# main_board.net
KiCad netlist of a schematic drawn in EAGLE
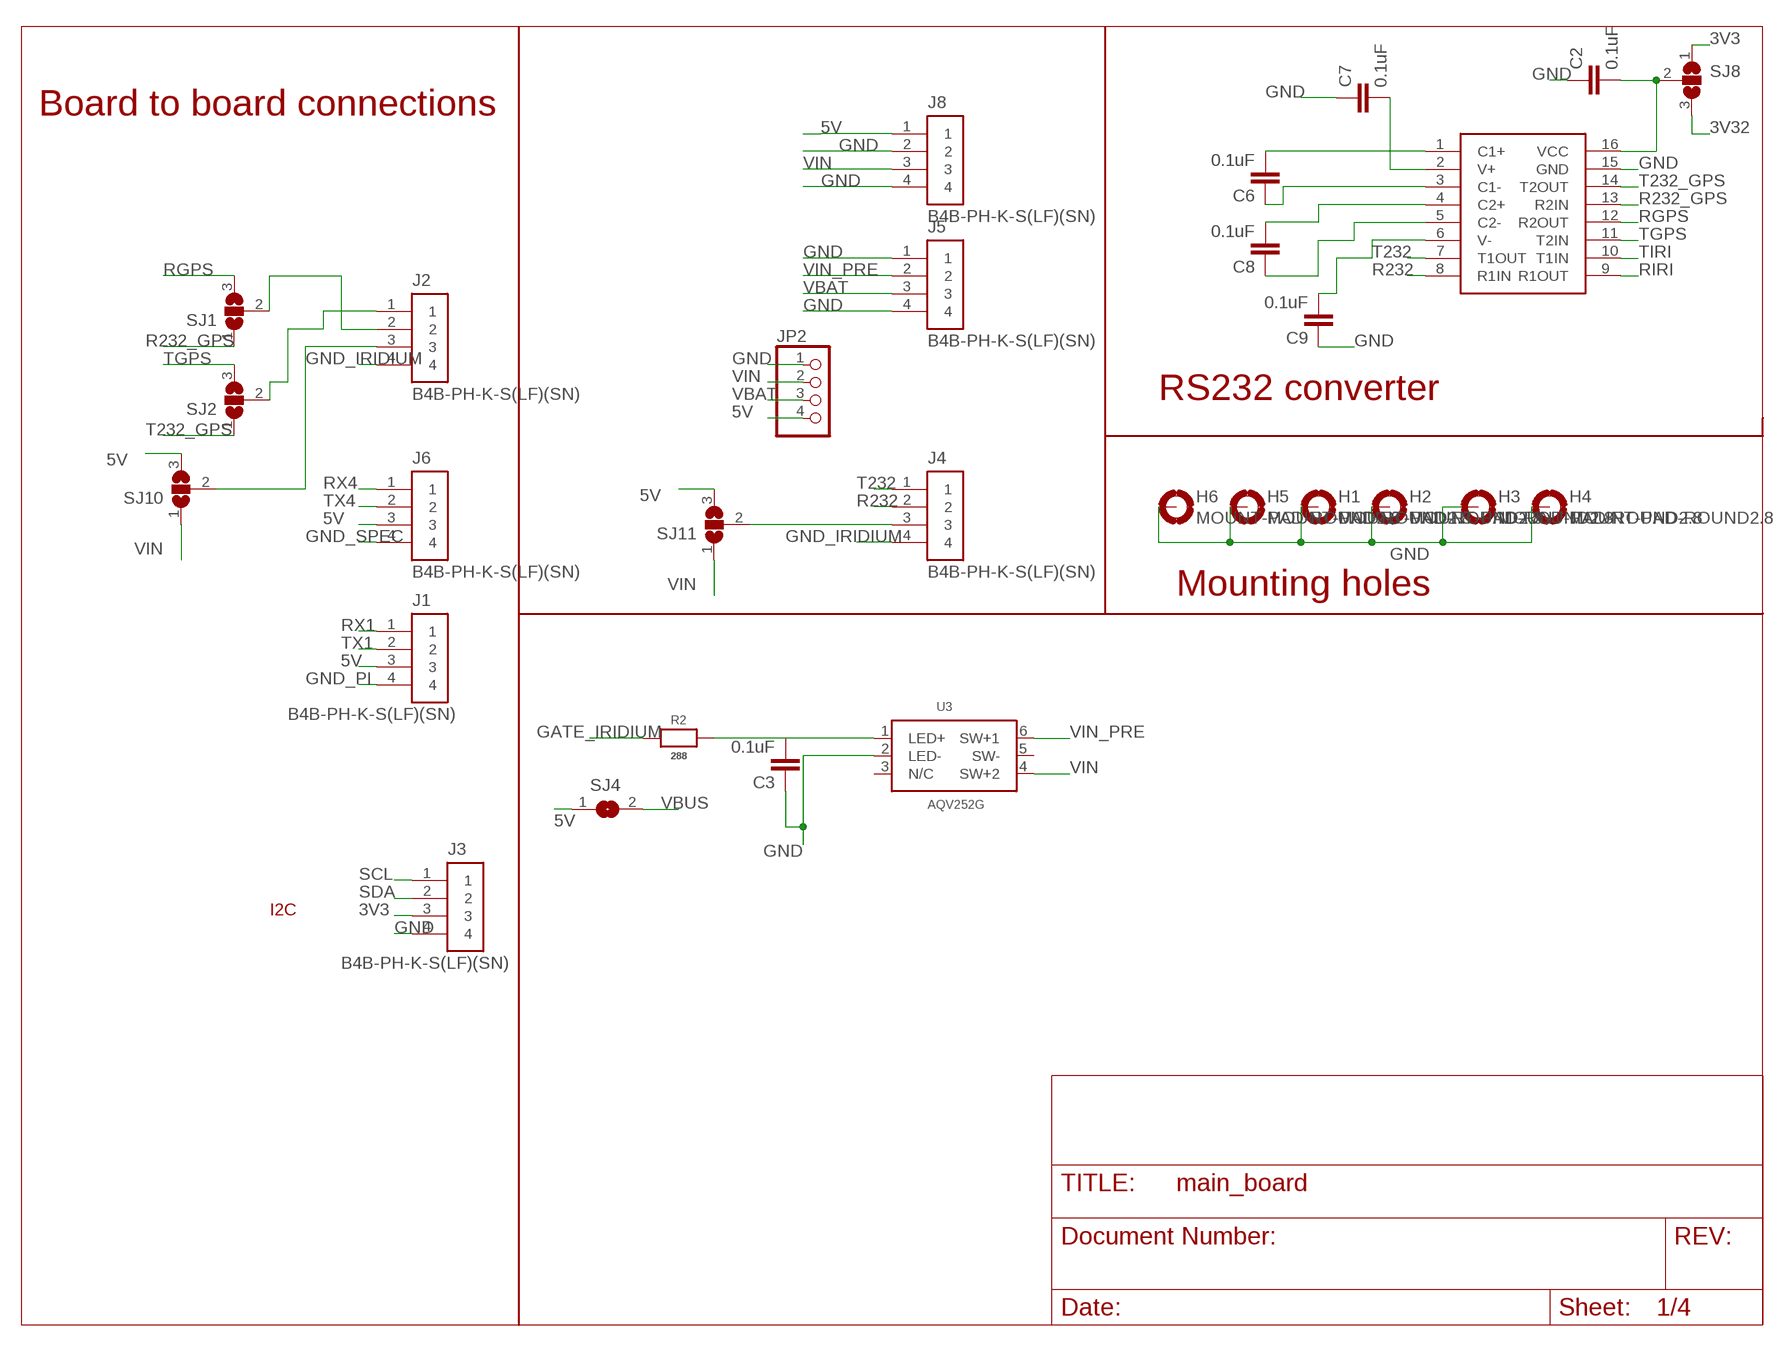
[diagram p0: schematic, sheet 1]
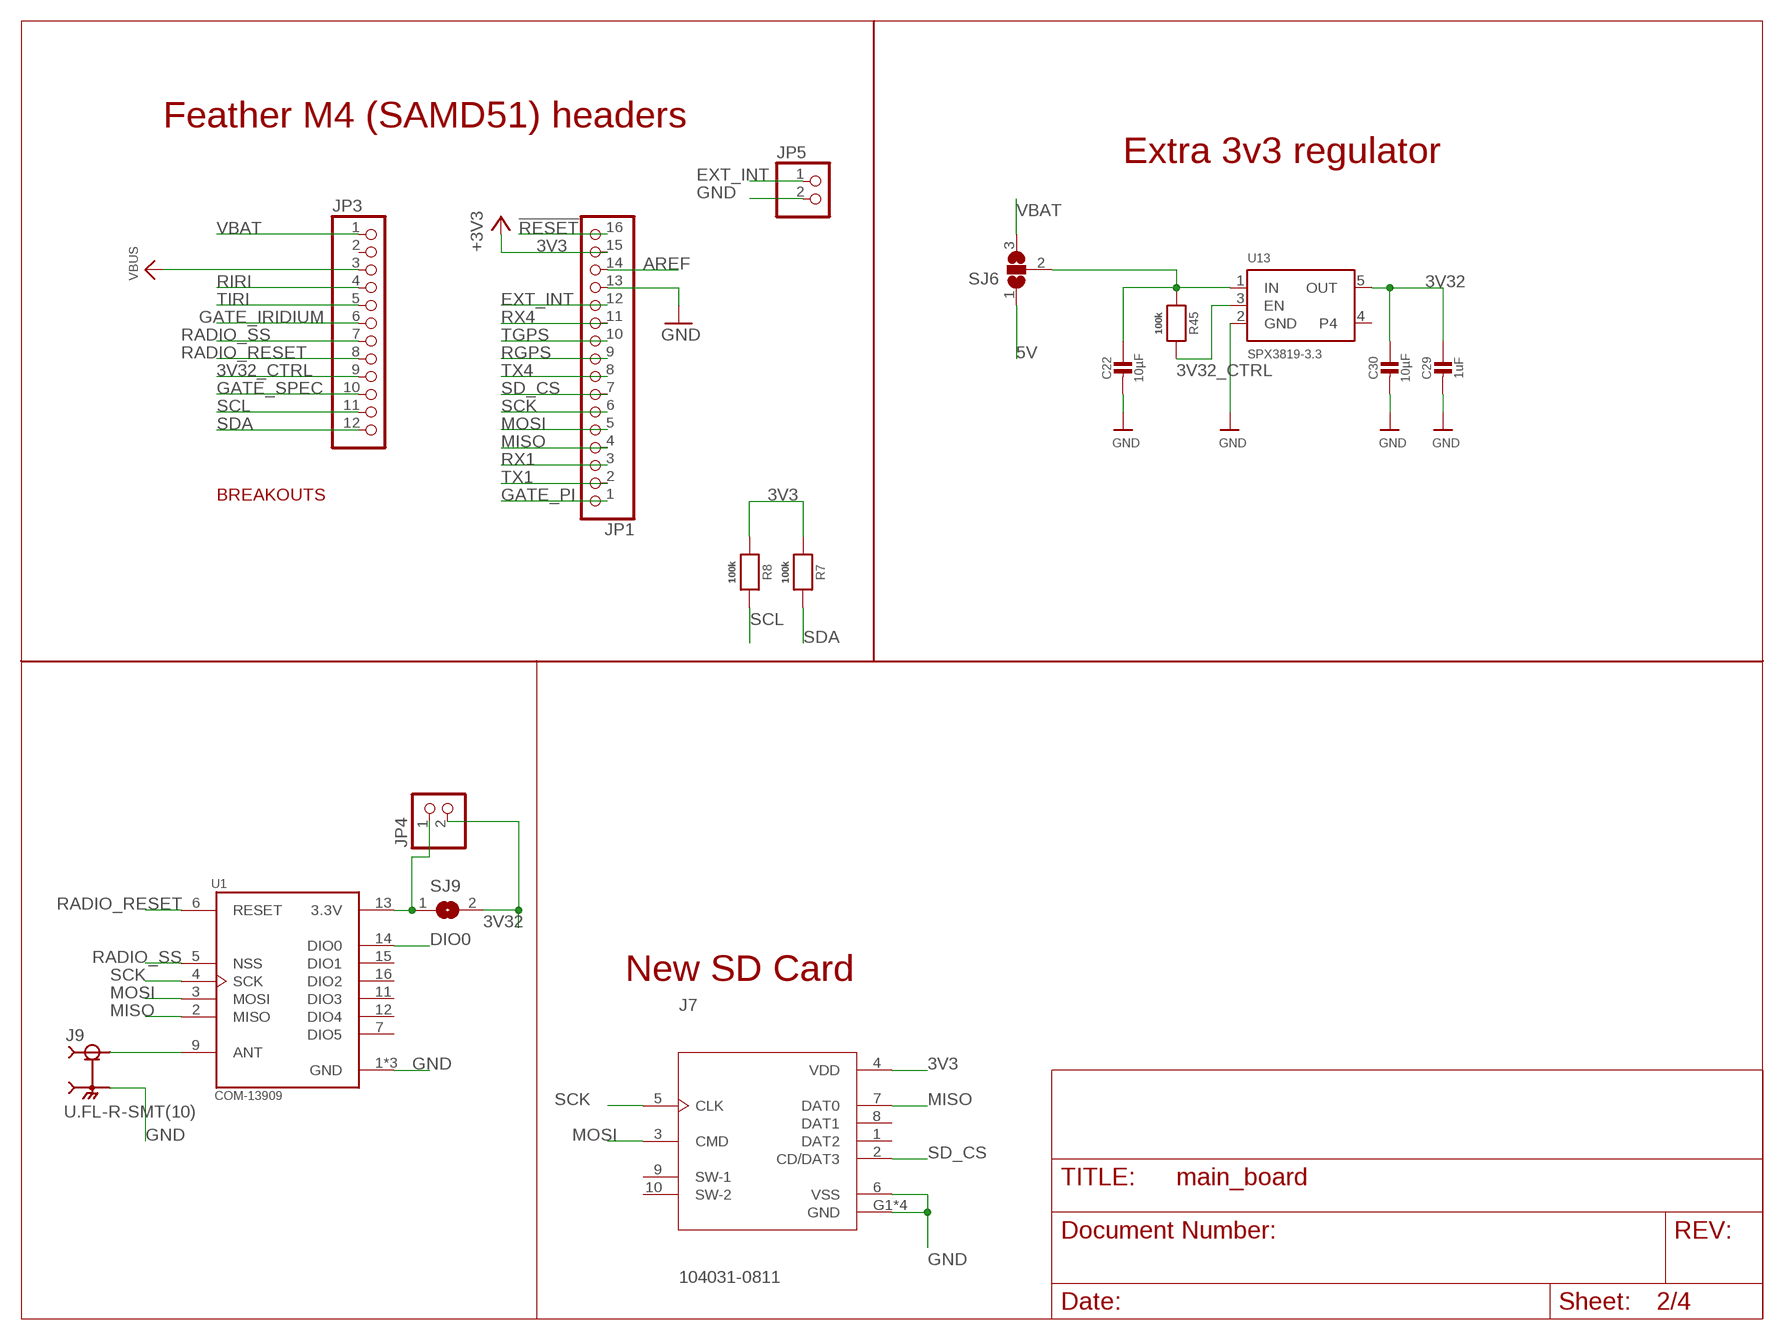
[diagram p1: schematic, sheet 2]
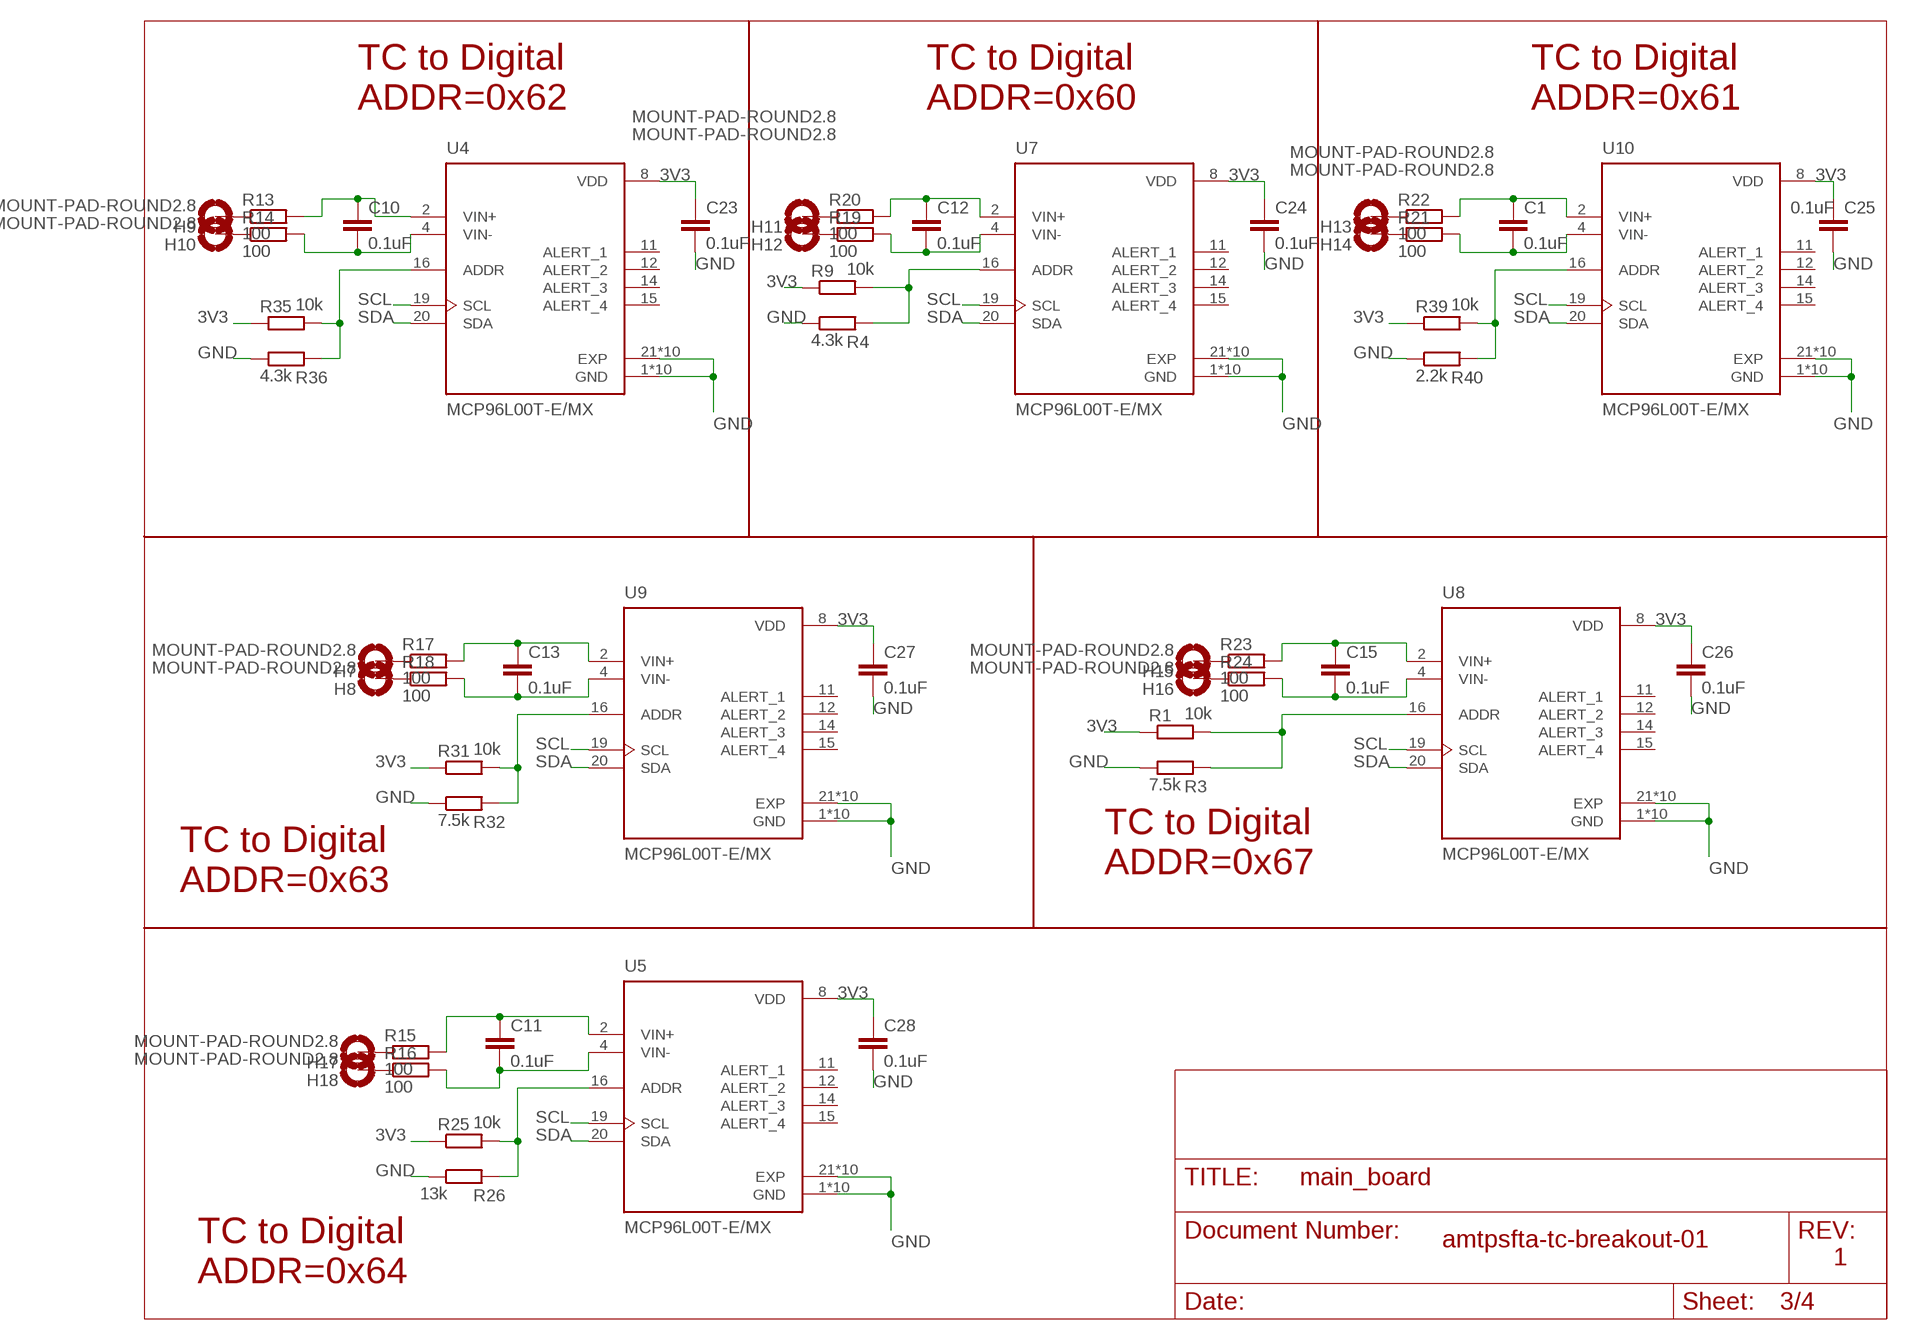
[diagram p2: schematic, sheet 3]
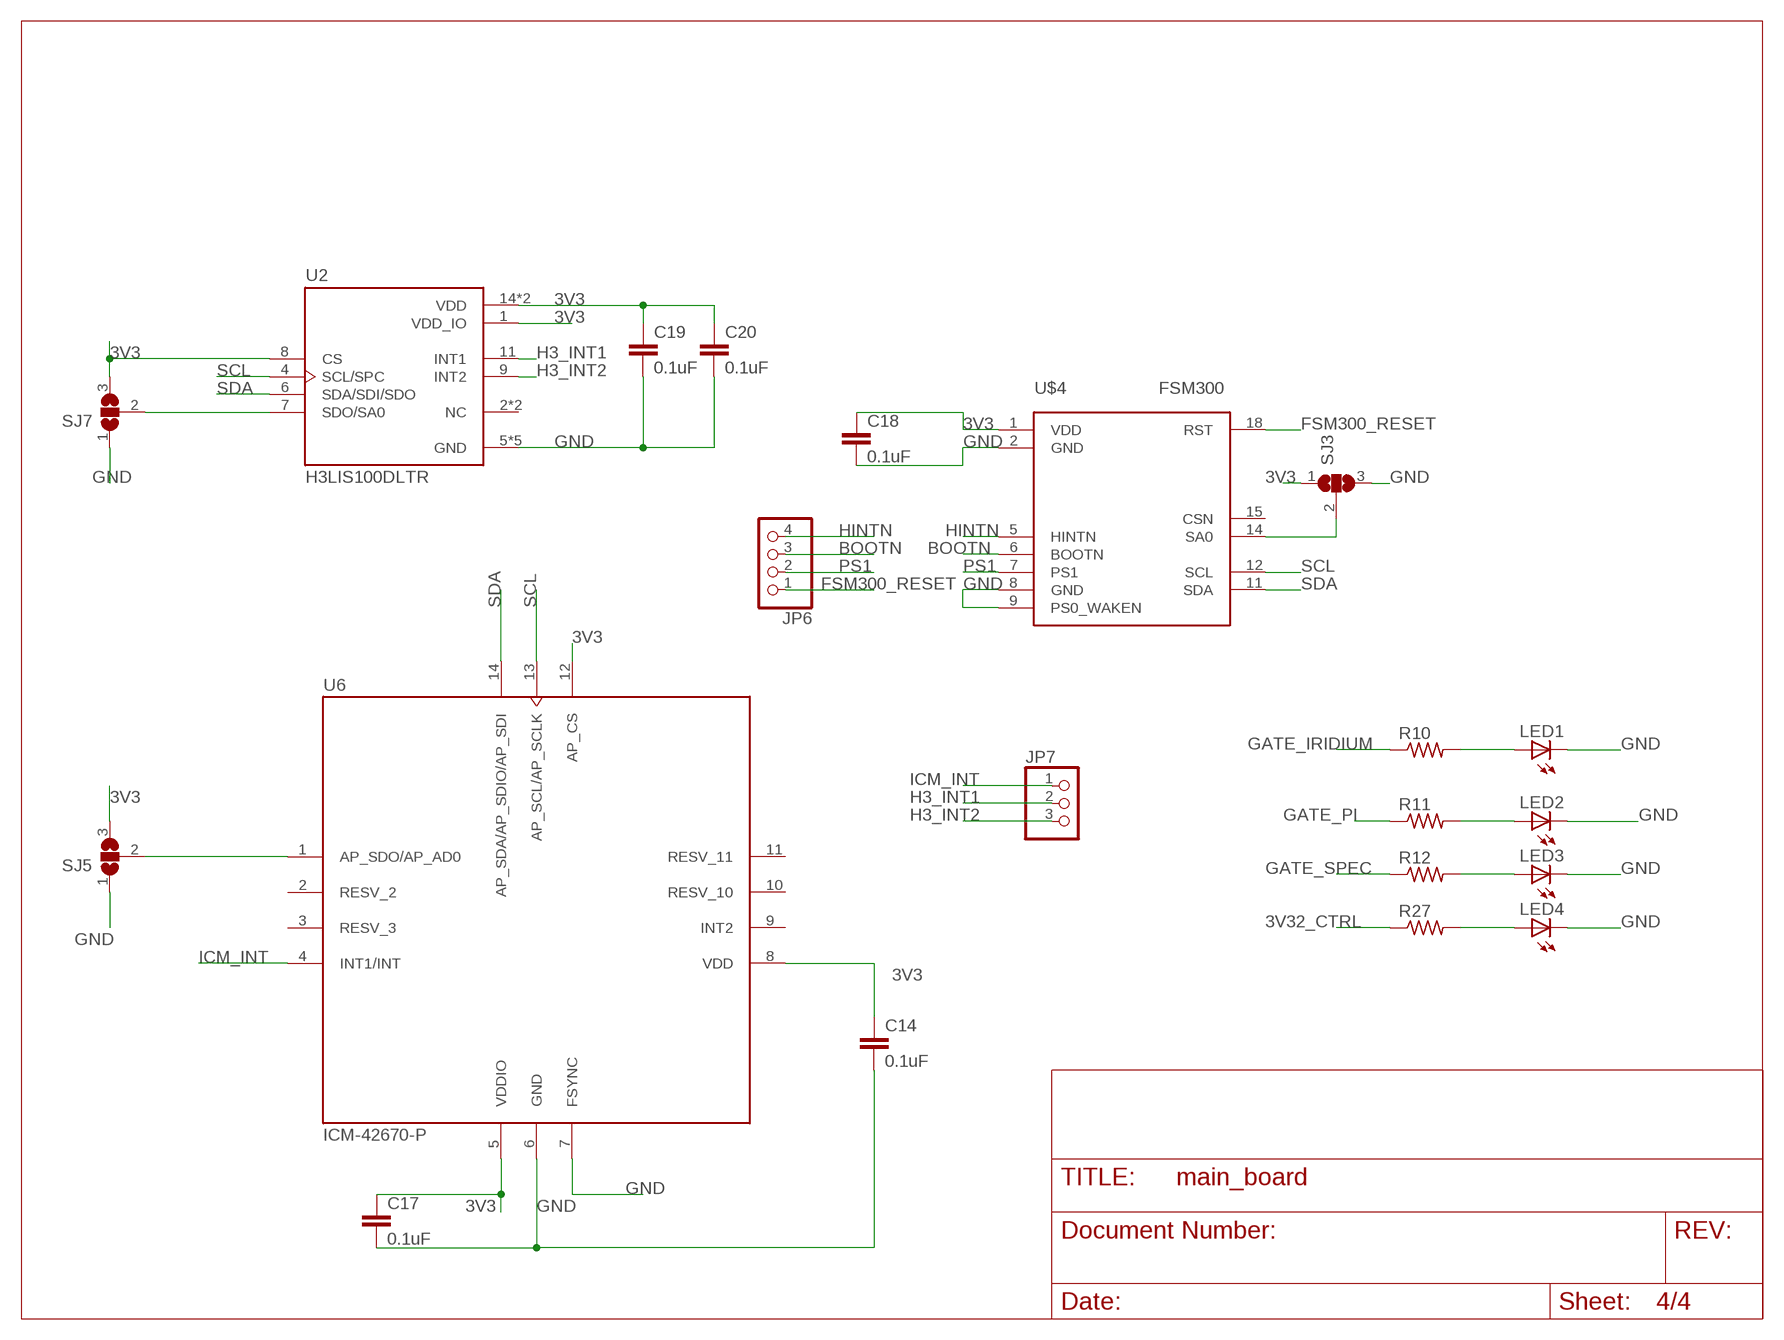
[diagram p3: schematic, sheet 4]

(export (version "E")
  (design (tool "Eeschema 10.0.6"))
  (components
    (comp (ref "C2")
      (value "0.1uF")
      (footprint "eagle-import:C0603")
      (libsource (lib "eagle-import") (part "C-EUC0603"))
    )
    (comp (ref "C3")
      (value "0.1uF")
      (footprint "eagle-import:C0603")
      (libsource (lib "eagle-import") (part "C-EUC0603"))
    )
    (comp (ref "C6")
      (value "0.1uF")
      (footprint "eagle-import:C0603")
      (libsource (lib "eagle-import") (part "C-EUC0603"))
    )
    (comp (ref "C7")
      (value "0.1uF")
      (footprint "eagle-import:C0603")
      (libsource (lib "eagle-import") (part "C-EUC0603"))
    )
    (comp (ref "C8")
      (value "0.1uF")
      (footprint "eagle-import:C0603")
      (libsource (lib "eagle-import") (part "C-EUC0603"))
    )
    (comp (ref "C9")
      (value "0.1uF")
      (footprint "eagle-import:C0603")
      (libsource (lib "eagle-import") (part "C-EUC0603"))
    )
    (comp (ref "H1")
      (value "MOUNT-PAD-ROUND2.8")
      (footprint "eagle-import:2,8-PAD")
      (libsource (lib "eagle-import") (part "MOUNT-PAD-ROUND2.8"))
    )
    (comp (ref "H2")
      (value "MOUNT-PAD-ROUND2.8")
      (footprint "eagle-import:2,8-PAD")
      (libsource (lib "eagle-import") (part "MOUNT-PAD-ROUND2.8"))
    )
    (comp (ref "H3")
      (value "MOUNT-PAD-ROUND2.8")
      (footprint "eagle-import:2,8-PAD")
      (libsource (lib "eagle-import") (part "MOUNT-PAD-ROUND2.8"))
    )
    (comp (ref "H4")
      (value "MOUNT-PAD-ROUND2.8")
      (footprint "eagle-import:2,8-PAD")
      (libsource (lib "eagle-import") (part "MOUNT-PAD-ROUND2.8"))
    )
    (comp (ref "H5")
      (value "MOUNT-PAD-ROUND2.8")
      (footprint "eagle-import:2,8-PAD")
      (libsource (lib "eagle-import") (part "MOUNT-PAD-ROUND2.8"))
    )
    (comp (ref "H6")
      (value "MOUNT-PAD-ROUND2.8")
      (footprint "eagle-import:2,8-PAD")
      (libsource (lib "eagle-import") (part "MOUNT-PAD-ROUND2.8"))
    )
    (comp (ref "J1")
      (value "B4B-PH-K-S(LF)(SN)")
      (footprint "eagle-import:JST_B4B-PH-K-S(LF)(SN)")
      (fields (field (name "DIGI-KEY_PART_NUMBER") "455-1706-ND") (field (name "MF") "JST"))
      (libsource (lib "eagle-import") (part "B4B-PH-K-S(LF)(SN)"))
    )
    (comp (ref "J2")
      (value "B4B-PH-K-S(LF)(SN)")
      (footprint "eagle-import:JST_B4B-PH-K-S(LF)(SN)")
      (fields (field (name "DIGI-KEY_PART_NUMBER") "455-1706-ND") (field (name "MF") "JST"))
      (libsource (lib "eagle-import") (part "B4B-PH-K-S(LF)(SN)"))
    )
    (comp (ref "J3")
      (value "B4B-PH-K-S(LF)(SN)")
      (footprint "eagle-import:JST_B4B-PH-K-S(LF)(SN)")
      (fields (field (name "DIGI-KEY_PART_NUMBER") "455-1706-ND") (field (name "MF") "JST"))
      (libsource (lib "eagle-import") (part "B4B-PH-K-S(LF)(SN)"))
    )
    (comp (ref "J4")
      (value "B4B-PH-K-S(LF)(SN)")
      (footprint "eagle-import:JST_B4B-PH-K-S(LF)(SN)")
      (fields (field (name "DIGI-KEY_PART_NUMBER") "455-1706-ND") (field (name "MF") "JST"))
      (libsource (lib "eagle-import") (part "B4B-PH-K-S(LF)(SN)"))
    )
    (comp (ref "J5")
      (value "B4B-PH-K-S(LF)(SN)")
      (footprint "eagle-import:JST_B4B-PH-K-S(LF)(SN)")
      (fields (field (name "DIGI-KEY_PART_NUMBER") "455-1706-ND") (field (name "MF") "JST"))
      (libsource (lib "eagle-import") (part "B4B-PH-K-S(LF)(SN)"))
    )
    (comp (ref "J6")
      (value "B4B-PH-K-S(LF)(SN)")
      (footprint "eagle-import:JST_B4B-PH-K-S(LF)(SN)")
      (fields (field (name "DIGI-KEY_PART_NUMBER") "455-1706-ND") (field (name "MF") "JST"))
      (libsource (lib "eagle-import") (part "B4B-PH-K-S(LF)(SN)"))
    )
    (comp (ref "J8")
      (value "B4B-PH-K-S(LF)(SN)")
      (footprint "eagle-import:JST_B4B-PH-K-S(LF)(SN)")
      (fields (field (name "DIGI-KEY_PART_NUMBER") "455-1706-ND") (field (name "MF") "JST"))
      (libsource (lib "eagle-import") (part "B4B-PH-K-S(LF)(SN)"))
    )
    (comp (ref "JP2")
      (value "PINHD-1X4")
      (footprint "eagle-import:1X04")
      (libsource (lib "eagle-import") (part "PINHD-1X4"))
    )
    (comp (ref "R2")
      (value "288")
      (footprint "eagle-import:0603-NO")
      (libsource (lib "eagle-import") (part "RESISTOR_0603_NOOUT"))
    )
    (comp (ref "SJ1")
      (value "SJ2W")
      (footprint "eagle-import:SJ_2")
      (libsource (lib "eagle-import") (part "SJ2W"))
    )
    (comp (ref "SJ2")
      (value "SJ2W")
      (footprint "eagle-import:SJ_2")
      (libsource (lib "eagle-import") (part "SJ2W"))
    )
    (comp (ref "SJ4") (value "SJ") (footprint "eagle-import:SJ") (libsource (lib "eagle-import") (part "SJ")))
    (comp (ref "SJ8")
      (value "SJ2W")
      (footprint "eagle-import:SJ_2")
      (libsource (lib "eagle-import") (part "SJ2W"))
    )
    (comp (ref "SJ10")
      (value "SJ2W")
      (footprint "eagle-import:SJ_2")
      (libsource (lib "eagle-import") (part "SJ2W"))
    )
    (comp (ref "SJ11")
      (value "SJ2W")
      (footprint "eagle-import:SJ_2")
      (libsource (lib "eagle-import") (part "SJ2W"))
    )
    (comp (ref "U3")
      (value "AQV252G")
      (footprint "eagle-import:SOP6")
      (fields (field (name "DIGI-KEY_PART_NUMBER") "255-1791-5-ND") (field (name "MF") "Panasonic"))
      (libsource (lib "eagle-import") (part "AQV252G"))
    )
    (comp (ref "U11")
      (value "UM3232EEAE")
      (footprint "eagle-import:RQ_16_ADI")
      (libsource (lib "eagle-import") (part "UM3232EEAE"))
    )
    (comp (ref "C1")
      (value "0.1uF")
      (footprint "eagle-import:C0603")
      (libsource (lib "eagle-import") (part "C-EUC0603"))
    )
    (comp (ref "C10")
      (value "0.1uF")
      (footprint "eagle-import:C0603")
      (libsource (lib "eagle-import") (part "C-EUC0603"))
    )
    (comp (ref "C11")
      (value "0.1uF")
      (footprint "eagle-import:C0603")
      (libsource (lib "eagle-import") (part "C-EUC0603"))
    )
    (comp (ref "C12")
      (value "0.1uF")
      (footprint "eagle-import:C0603")
      (libsource (lib "eagle-import") (part "C-EUC0603"))
    )
    (comp (ref "C13")
      (value "0.1uF")
      (footprint "eagle-import:C0603")
      (libsource (lib "eagle-import") (part "C-EUC0603"))
    )
    (comp (ref "C15")
      (value "0.1uF")
      (footprint "eagle-import:C0603")
      (libsource (lib "eagle-import") (part "C-EUC0603"))
    )
    (comp (ref "C23")
      (value "0.1uF")
      (footprint "eagle-import:C0603")
      (libsource (lib "eagle-import") (part "C-EUC0603"))
    )
    (comp (ref "C24")
      (value "0.1uF")
      (footprint "eagle-import:C0603")
      (libsource (lib "eagle-import") (part "C-EUC0603"))
    )
    (comp (ref "C25")
      (value "0.1uF")
      (footprint "eagle-import:C0603")
      (libsource (lib "eagle-import") (part "C-EUC0603"))
    )
    (comp (ref "C26")
      (value "0.1uF")
      (footprint "eagle-import:C0603")
      (libsource (lib "eagle-import") (part "C-EUC0603"))
    )
    (comp (ref "C27")
      (value "0.1uF")
      (footprint "eagle-import:C0603")
      (libsource (lib "eagle-import") (part "C-EUC0603"))
    )
    (comp (ref "C28")
      (value "0.1uF")
      (footprint "eagle-import:C0603")
      (libsource (lib "eagle-import") (part "C-EUC0603"))
    )
    (comp (ref "H7")
      (value "MOUNT-PAD-ROUND2.8")
      (footprint "eagle-import:2,8-PAD")
      (libsource (lib "eagle-import") (part "MOUNT-PAD-ROUND2.8"))
    )
    (comp (ref "H8")
      (value "MOUNT-PAD-ROUND2.8")
      (footprint "eagle-import:2,8-PAD")
      (libsource (lib "eagle-import") (part "MOUNT-PAD-ROUND2.8"))
    )
    (comp (ref "H9")
      (value "MOUNT-PAD-ROUND2.8")
      (footprint "eagle-import:2,8-PAD")
      (libsource (lib "eagle-import") (part "MOUNT-PAD-ROUND2.8"))
    )
    (comp (ref "H10")
      (value "MOUNT-PAD-ROUND2.8")
      (footprint "eagle-import:2,8-PAD")
      (libsource (lib "eagle-import") (part "MOUNT-PAD-ROUND2.8"))
    )
    (comp (ref "H11")
      (value "MOUNT-PAD-ROUND2.8")
      (footprint "eagle-import:2,8-PAD")
      (libsource (lib "eagle-import") (part "MOUNT-PAD-ROUND2.8"))
    )
    (comp (ref "H12")
      (value "MOUNT-PAD-ROUND2.8")
      (footprint "eagle-import:2,8-PAD")
      (libsource (lib "eagle-import") (part "MOUNT-PAD-ROUND2.8"))
    )
    (comp (ref "H13")
      (value "MOUNT-PAD-ROUND2.8")
      (footprint "eagle-import:2,8-PAD")
      (libsource (lib "eagle-import") (part "MOUNT-PAD-ROUND2.8"))
    )
    (comp (ref "H14")
      (value "MOUNT-PAD-ROUND2.8")
      (footprint "eagle-import:2,8-PAD")
      (libsource (lib "eagle-import") (part "MOUNT-PAD-ROUND2.8"))
    )
    (comp (ref "H15")
      (value "MOUNT-PAD-ROUND2.8")
      (footprint "eagle-import:2,8-PAD")
      (libsource (lib "eagle-import") (part "MOUNT-PAD-ROUND2.8"))
    )
    (comp (ref "H16")
      (value "MOUNT-PAD-ROUND2.8")
      (footprint "eagle-import:2,8-PAD")
      (libsource (lib "eagle-import") (part "MOUNT-PAD-ROUND2.8"))
    )
    (comp (ref "H17")
      (value "MOUNT-PAD-ROUND2.8")
      (footprint "eagle-import:2,8-PAD")
      (libsource (lib "eagle-import") (part "MOUNT-PAD-ROUND2.8"))
    )
    (comp (ref "H18")
      (value "MOUNT-PAD-ROUND2.8")
      (footprint "eagle-import:2,8-PAD")
      (libsource (lib "eagle-import") (part "MOUNT-PAD-ROUND2.8"))
    )
    (comp (ref "R1")
      (value "10k")
      (footprint "eagle-import:R0603")
      (libsource (lib "eagle-import") (part "R-EU_R0603"))
    )
    (comp (ref "R3")
      (value "7.5k")
      (footprint "eagle-import:R0603")
      (libsource (lib "eagle-import") (part "R-EU_R0603"))
    )
    (comp (ref "R4")
      (value "4.3k")
      (footprint "eagle-import:R0603")
      (libsource (lib "eagle-import") (part "R-EU_R0603"))
    )
    (comp (ref "R9")
      (value "10k")
      (footprint "eagle-import:R0603")
      (libsource (lib "eagle-import") (part "R-EU_R0603"))
    )
    (comp (ref "R13")
      (value "100")
      (footprint "eagle-import:R0603")
      (libsource (lib "eagle-import") (part "R-EU_R0603"))
    )
    (comp (ref "R14")
      (value "100")
      (footprint "eagle-import:R0603")
      (libsource (lib "eagle-import") (part "R-EU_R0603"))
    )
    (comp (ref "R15")
      (value "100")
      (footprint "eagle-import:R0603")
      (libsource (lib "eagle-import") (part "R-EU_R0603"))
    )
    (comp (ref "R16")
      (value "100")
      (footprint "eagle-import:R0603")
      (libsource (lib "eagle-import") (part "R-EU_R0603"))
    )
    (comp (ref "R17")
      (value "100")
      (footprint "eagle-import:R0603")
      (libsource (lib "eagle-import") (part "R-EU_R0603"))
    )
    (comp (ref "R18")
      (value "100")
      (footprint "eagle-import:R0603")
      (libsource (lib "eagle-import") (part "R-EU_R0603"))
    )
    (comp (ref "R19")
      (value "100")
      (footprint "eagle-import:R0603")
      (libsource (lib "eagle-import") (part "R-EU_R0603"))
    )
    (comp (ref "R20")
      (value "100")
      (footprint "eagle-import:R0603")
      (libsource (lib "eagle-import") (part "R-EU_R0603"))
    )
    (comp (ref "R21")
      (value "100")
      (footprint "eagle-import:R0603")
      (libsource (lib "eagle-import") (part "R-EU_R0603"))
    )
    (comp (ref "R22")
      (value "100")
      (footprint "eagle-import:R0603")
      (libsource (lib "eagle-import") (part "R-EU_R0603"))
    )
    (comp (ref "R23")
      (value "100")
      (footprint "eagle-import:R0603")
      (libsource (lib "eagle-import") (part "R-EU_R0603"))
    )
    (comp (ref "R24")
      (value "100")
      (footprint "eagle-import:R0603")
      (libsource (lib "eagle-import") (part "R-EU_R0603"))
    )
    (comp (ref "R25")
      (value "10k")
      (footprint "eagle-import:R0603")
      (libsource (lib "eagle-import") (part "R-EU_R0603"))
    )
    (comp (ref "R26")
      (value "13k")
      (footprint "eagle-import:R0603")
      (libsource (lib "eagle-import") (part "R-EU_R0603"))
    )
    (comp (ref "R31")
      (value "10k")
      (footprint "eagle-import:R0603")
      (libsource (lib "eagle-import") (part "R-EU_R0603"))
    )
    (comp (ref "R32")
      (value "7.5k")
      (footprint "eagle-import:R0603")
      (libsource (lib "eagle-import") (part "R-EU_R0603"))
    )
    (comp (ref "R35")
      (value "10k")
      (footprint "eagle-import:R0603")
      (libsource (lib "eagle-import") (part "R-EU_R0603"))
    )
    (comp (ref "R36")
      (value "4.3k")
      (footprint "eagle-import:R0603")
      (libsource (lib "eagle-import") (part "R-EU_R0603"))
    )
    (comp (ref "R39")
      (value "10k")
      (footprint "eagle-import:R0603")
      (libsource (lib "eagle-import") (part "R-EU_R0603"))
    )
    (comp (ref "R40")
      (value "2.2k")
      (footprint "eagle-import:R0603")
      (libsource (lib "eagle-import") (part "R-EU_R0603"))
    )
    (comp (ref "U4")
      (value "MCP96L00T-E/MX")
      (footprint "eagle-import:QFN65P500X500X100-21N_MCP96L00T-E_MX")
      (fields
        (field (name "DIGI-KEY_PART_NUMBER") "MCP96L00T-E/MXCT-ND")
        (field (name "MF") "Microchip Technology")
      )
      (libsource (lib "eagle-import") (part "MCP96L00T-E/MX"))
    )
    (comp (ref "U5")
      (value "MCP96L00T-E/MX")
      (footprint "eagle-import:QFN65P500X500X100-21N_MCP96L00T-E_MX")
      (fields
        (field (name "DIGI-KEY_PART_NUMBER") "MCP96L00T-E/MXCT-ND")
        (field (name "MF") "Microchip Technology")
      )
      (libsource (lib "eagle-import") (part "MCP96L00T-E/MX"))
    )
    (comp (ref "U7")
      (value "MCP96L00T-E/MX")
      (footprint "eagle-import:QFN65P500X500X100-21N_MCP96L00T-E_MX")
      (fields
        (field (name "DIGI-KEY_PART_NUMBER") "MCP96L00T-E/MXCT-ND")
        (field (name "MF") "Microchip Technology")
      )
      (libsource (lib "eagle-import") (part "MCP96L00T-E/MX"))
    )
    (comp (ref "U8")
      (value "MCP96L00T-E/MX")
      (footprint "eagle-import:QFN65P500X500X100-21N_MCP96L00T-E_MX")
      (fields
        (field (name "DIGI-KEY_PART_NUMBER") "MCP96L00T-E/MXCT-ND")
        (field (name "MF") "Microchip Technology")
      )
      (libsource (lib "eagle-import") (part "MCP96L00T-E/MX"))
    )
    (comp (ref "U9")
      (value "MCP96L00T-E/MX")
      (footprint "eagle-import:QFN65P500X500X100-21N_MCP96L00T-E_MX")
      (fields
        (field (name "DIGI-KEY_PART_NUMBER") "MCP96L00T-E/MXCT-ND")
        (field (name "MF") "Microchip Technology")
      )
      (libsource (lib "eagle-import") (part "MCP96L00T-E/MX"))
    )
    (comp (ref "U10")
      (value "MCP96L00T-E/MX")
      (footprint "eagle-import:QFN65P500X500X100-21N_MCP96L00T-E_MX")
      (fields
        (field (name "DIGI-KEY_PART_NUMBER") "MCP96L00T-E/MXCT-ND")
        (field (name "MF") "Microchip Technology")
      )
      (libsource (lib "eagle-import") (part "MCP96L00T-E/MX"))
    )
    (comp (ref "C22")
      (value "10µF")
      (footprint "eagle-import:0805-NO")
      (libsource (lib "eagle-import") (part "CAP_CERAMIC0805-NOOUTLINE"))
    )
    (comp (ref "C29")
      (value "1uF")
      (footprint "eagle-import:0603-NO")
      (libsource (lib "eagle-import") (part "CAP_CERAMIC0603_NO"))
    )
    (comp (ref "C30")
      (value "10µF")
      (footprint "eagle-import:0805-NO")
      (libsource (lib "eagle-import") (part "CAP_CERAMIC0805-NOOUTLINE"))
    )
    (comp (ref "J7")
      (value "104031-0811")
      (footprint "eagle-import:MOLEX_104031-0811")
      (fields (field (name "DIGI-KEY_PART_NUMBER") "WM6357TR-ND") (field (name "MF") "Molex"))
      (libsource (lib "eagle-import") (part "104031-0811"))
    )
    (comp (ref "J9")
      (value "U.FL-R-SMT(10)")
      (footprint "eagle-import:HRS_U.FL-R-SMT(10)")
      (fields (field (name "DIGI-KEY_PART_NUMBER") "H9161TR-ND") (field (name "MF") "Hirose Electric Co Ltd"))
      (libsource (lib "eagle-import") (part "U.FL-R-SMT(10)"))
    )
    (comp (ref "JP1")
      (value "HEADER-1X16ROUND")
      (footprint "eagle-import:1X16_ROUND")
      (libsource (lib "eagle-import") (part "HEADER-1X16ROUND"))
    )
    (comp (ref "JP3")
      (value "HEADER-1X12")
      (footprint "eagle-import:1X12_ROUND")
      (libsource (lib "eagle-import") (part "HEADER-1X12"))
    )
    (comp (ref "JP4")
      (value "PINHD-1X2")
      (footprint "eagle-import:1X02")
      (libsource (lib "eagle-import") (part "PINHD-1X2"))
    )
    (comp (ref "JP5")
      (value "PINHD-1X2")
      (footprint "eagle-import:1X02")
      (libsource (lib "eagle-import") (part "PINHD-1X2"))
    )
    (comp (ref "R7")
      (value "100k")
      (footprint "eagle-import:0603-NO")
      (libsource (lib "eagle-import") (part "RESISTOR_0603_NOOUT"))
    )
    (comp (ref "R8")
      (value "100k")
      (footprint "eagle-import:0603-NO")
      (libsource (lib "eagle-import") (part "RESISTOR_0603_NOOUT"))
    )
    (comp (ref "R45")
      (value "100k")
      (footprint "eagle-import:0603-NO")
      (libsource (lib "eagle-import") (part "RESISTOR_0603_NOOUT"))
    )
    (comp (ref "SJ6")
      (value "SJ2W")
      (footprint "eagle-import:SJ_2")
      (libsource (lib "eagle-import") (part "SJ2W"))
    )
    (comp (ref "SJ9") (value "SJ") (footprint "eagle-import:SJ") (libsource (lib "eagle-import") (part "SJ")))
    (comp (ref "U1")
      (value "COM-13909")
      (footprint "eagle-import:MOD_COM-13909")
      (fields (field (name "DIGI-KEY_PART_NUMBER") "1568-1394-ND") (field (name "MF") "SparkFun Electronics"))
      (libsource (lib "eagle-import") (part "COM-13909"))
    )
    (comp (ref "U13")
      (value "SPX3819-3.3")
      (footprint "eagle-import:SOT23-5")
      (libsource (lib "eagle-import") (part "VREG_SOT23-5"))
    )
    (comp (ref "C14")
      (value "0.1uF")
      (footprint "eagle-import:C0603")
      (libsource (lib "eagle-import") (part "C-EUC0603"))
    )
    (comp (ref "C17")
      (value "0.1uF")
      (footprint "eagle-import:C0603")
      (libsource (lib "eagle-import") (part "C-EUC0603"))
    )
    (comp (ref "C18")
      (value "0.1uF")
      (footprint "eagle-import:C0603")
      (libsource (lib "eagle-import") (part "C-EUC0603"))
    )
    (comp (ref "C19")
      (value "0.1uF")
      (footprint "eagle-import:C0603")
      (libsource (lib "eagle-import") (part "C-EUC0603"))
    )
    (comp (ref "C20")
      (value "0.1uF")
      (footprint "eagle-import:C0603")
      (libsource (lib "eagle-import") (part "C-EUC0603"))
    )
    (comp (ref "JP6")
      (value "PINHD-1X4")
      (footprint "eagle-import:1X04")
      (libsource (lib "eagle-import") (part "PINHD-1X4"))
    )
    (comp (ref "JP7")
      (value "PINHD-1X3")
      (footprint "eagle-import:1X03")
      (libsource (lib "eagle-import") (part "PINHD-1X3"))
    )
    (comp (ref "LED1")
      (value "LEDCHIPLED_0603")
      (footprint "eagle-import:CHIPLED_0603")
      (libsource (lib "eagle-import") (part "LEDCHIPLED_0603"))
    )
    (comp (ref "LED2")
      (value "LEDCHIPLED_0603")
      (footprint "eagle-import:CHIPLED_0603")
      (libsource (lib "eagle-import") (part "LEDCHIPLED_0603"))
    )
    (comp (ref "LED3")
      (value "LEDCHIPLED_0603")
      (footprint "eagle-import:CHIPLED_0603")
      (libsource (lib "eagle-import") (part "LEDCHIPLED_0603"))
    )
    (comp (ref "LED4")
      (value "LEDCHIPLED_0603")
      (footprint "eagle-import:CHIPLED_0603")
      (libsource (lib "eagle-import") (part "LEDCHIPLED_0603"))
    )
    (comp (ref "R10")
      (value "R-US_R0603")
      (footprint "eagle-import:R0603")
      (libsource (lib "eagle-import") (part "R-US_R0603"))
    )
    (comp (ref "R11")
      (value "R-US_R0603")
      (footprint "eagle-import:R0603")
      (libsource (lib "eagle-import") (part "R-US_R0603"))
    )
    (comp (ref "R12")
      (value "R-US_R0603")
      (footprint "eagle-import:R0603")
      (libsource (lib "eagle-import") (part "R-US_R0603"))
    )
    (comp (ref "R27")
      (value "R-US_R0603")
      (footprint "eagle-import:R0603")
      (libsource (lib "eagle-import") (part "R-US_R0603"))
    )
    (comp (ref "SJ3")
      (value "SJ2W")
      (footprint "eagle-import:SJ_2")
      (libsource (lib "eagle-import") (part "SJ2W"))
    )
    (comp (ref "SJ5")
      (value "SJ2W")
      (footprint "eagle-import:SJ_2")
      (libsource (lib "eagle-import") (part "SJ2W"))
    )
    (comp (ref "SJ7")
      (value "SJ2W")
      (footprint "eagle-import:SJ_2")
      (libsource (lib "eagle-import") (part "SJ2W"))
    )
    (comp (ref "U$4")
      (value "FSM300")
      (footprint "eagle-import:FSM300_FOOTPRINT")
      (libsource (lib "eagle-import") (part "FSM300"))
    )
    (comp (ref "U2")
      (value "H3LIS100DLTR")
      (footprint "eagle-import:PQFN50P300X300X100-16N")
      (fields (field (name "DIGI-KEY_PART_NUMBER") "497-15697-2-ND") (field (name "MF") "STMicroelectronics"))
      (libsource (lib "eagle-import") (part "H3LIS100DLTR"))
    )
    (comp (ref "U6")
      (value "ICM-42670-P")
      (footprint "eagle-import:IC_ICM-42670-P")
      (fields
        (field (name "DIGI-KEY_PART_NUMBER") "1428-ICM-42670-PTR-ND")
        (field (name "MF") "TDK InvenSense")
      )
      (libsource (lib "eagle-import") (part "ICM-42670-P"))
    )
  )
  (nets
    (net (code "1") (name "3V3") (class "Default")
      (node (ref "C14") (pin "1") (pinfunction "1_1") (pintype "passive"))
      (node (ref "C17") (pin "1") (pinfunction "1_1") (pintype "passive"))
      (node (ref "C18") (pin "1") (pinfunction "1_1") (pintype "passive"))
      (node (ref "C19") (pin "1") (pinfunction "1_1") (pintype "passive"))
      (node (ref "C20") (pin "1") (pinfunction "1_1") (pintype "passive"))
      (node (ref "C23") (pin "1") (pinfunction "1_1") (pintype "passive"))
      (node (ref "C24") (pin "1") (pinfunction "1_1") (pintype "passive"))
      (node (ref "C25") (pin "1") (pinfunction "1_1") (pintype "passive"))
      (node (ref "C26") (pin "1") (pinfunction "1_1") (pintype "passive"))
      (node (ref "C27") (pin "1") (pinfunction "1_1") (pintype "passive"))
      (node (ref "C28") (pin "1") (pinfunction "1_1") (pintype "passive"))
      (node (ref "J3") (pin "3") (pinfunction "3_3") (pintype "passive"))
      (node (ref "J7") (pin "4") (pinfunction "VDD_4") (pintype "power_in"))
      (node (ref "JP1") (pin "15") (pinfunction "15_15") (pintype "passive"))
      (node (ref "R1") (pin "1") (pinfunction "1_1") (pintype "passive"))
      (node (ref "R25") (pin "1") (pinfunction "1_1") (pintype "passive"))
      (node (ref "R31") (pin "1") (pinfunction "1_1") (pintype "passive"))
      (node (ref "R35") (pin "1") (pinfunction "1_1") (pintype "passive"))
      (node (ref "R39") (pin "1") (pinfunction "1_1") (pintype "passive"))
      (node (ref "R7") (pin "1") (pinfunction "1_1") (pintype "passive"))
      (node (ref "R8") (pin "1") (pinfunction "1_1") (pintype "passive"))
      (node (ref "R9") (pin "1") (pinfunction "1_1") (pintype "passive"))
      (node (ref "SJ3") (pin "1") (pinfunction "1_1") (pintype "passive"))
      (node (ref "SJ5") (pin "3") (pinfunction "3_3") (pintype "passive"))
      (node (ref "SJ7") (pin "3") (pinfunction "3_3") (pintype "passive"))
      (node (ref "SJ8") (pin "1") (pinfunction "1_1") (pintype "passive"))
      (node (ref "U$4") (pin "1") (pinfunction "VDD_1") (pintype "bidirectional"))
      (node (ref "U10") (pin "8") (pinfunction "VDD_8") (pintype "power_in"))
      (node (ref "U2") (pin "1") (pinfunction "VDD_IO_1") (pintype "power_in"))
      (node (ref "U2") (pin "14") (pinfunction "VDD_14") (pintype "power_in"))
      (node (ref "U2") (pin "15") (pinfunction "VDD_15") (pintype "power_in"))
      (node (ref "U2") (pin "8") (pinfunction "CS_8") (pintype "input"))
      (node (ref "U4") (pin "8") (pinfunction "VDD_8") (pintype "power_in"))
      (node (ref "U5") (pin "8") (pinfunction "VDD_8") (pintype "power_in"))
      (node (ref "U6") (pin "12") (pinfunction "AP_CS_12") (pintype "input"))
      (node (ref "U6") (pin "5") (pinfunction "VDDIO_5") (pintype "power_in"))
      (node (ref "U6") (pin "8") (pinfunction "VDD_8") (pintype "power_in"))
      (node (ref "U7") (pin "8") (pinfunction "VDD_8") (pintype "power_in"))
      (node (ref "U8") (pin "8") (pinfunction "VDD_8") (pintype "power_in"))
      (node (ref "U9") (pin "8") (pinfunction "VDD_8") (pintype "power_in"))
    )
    (net (code "2") (name "3V32") (class "Default")
      (node (ref "C29") (pin "1") (pinfunction "1_1") (pintype "passive"))
      (node (ref "C30") (pin "1") (pinfunction "1_1") (pintype "passive"))
      (node (ref "JP4") (pin "2") (pinfunction "2_2") (pintype "passive"))
      (node (ref "SJ8") (pin "3") (pinfunction "3_3") (pintype "passive"))
      (node (ref "SJ9") (pin "2") (pinfunction "2_2") (pintype "passive"))
      (node (ref "U13") (pin "5") (pinfunction "OUT_5") (pintype "power_in"))
    )
    (net (code "3") (name "3V32_CTRL") (class "Default")
      (node (ref "JP3") (pin "9") (pinfunction "9_9") (pintype "passive"))
      (node (ref "R27") (pin "1") (pinfunction "1_1") (pintype "passive"))
      (node (ref "R45") (pin "2") (pinfunction "2_2") (pintype "passive"))
      (node (ref "U13") (pin "3") (pinfunction "EN_3") (pintype "input"))
    )
    (net (code "4") (name "5V") (class "Default")
      (node (ref "J1") (pin "3") (pinfunction "3_3") (pintype "passive"))
      (node (ref "J6") (pin "3") (pinfunction "3_3") (pintype "passive"))
      (node (ref "J8") (pin "1") (pinfunction "1_1") (pintype "passive"))
      (node (ref "JP2") (pin "4") (pinfunction "4_4") (pintype "passive"))
      (node (ref "SJ10") (pin "3") (pinfunction "3_3") (pintype "passive"))
      (node (ref "SJ11") (pin "3") (pinfunction "3_3") (pintype "passive"))
      (node (ref "SJ4") (pin "1") (pinfunction "1_1") (pintype "passive"))
      (node (ref "SJ6") (pin "1") (pinfunction "1_1") (pintype "passive"))
    )
    (net (code "5") (name "AREF") (class "Default")
      (node (ref "JP1") (pin "14") (pinfunction "14_14") (pintype "passive"))
    )
    (net (code "6") (name "BOOTN") (class "Default")
      (node (ref "JP6") (pin "3") (pinfunction "3_3") (pintype "passive"))
      (node (ref "U$4") (pin "6") (pinfunction "BOOTN_6") (pintype "bidirectional"))
    )
    (net (code "7") (name "DIO0") (class "Default")
      (node (ref "U1") (pin "14") (pinfunction "DIO0_14") (pintype "bidirectional"))
    )
    (net (code "8") (name "EXT_INT") (class "Default")
      (node (ref "JP1") (pin "12") (pinfunction "12_12") (pintype "passive"))
      (node (ref "JP5") (pin "1") (pinfunction "1_1") (pintype "passive"))
    )
    (net (code "9") (name "FSM300_RESET") (class "Default")
      (node (ref "JP6") (pin "1") (pinfunction "1_1") (pintype "passive"))
      (node (ref "U$4") (pin "18") (pinfunction "RST_18") (pintype "bidirectional"))
    )
    (net (code "10") (name "GATE_IRIDIUM") (class "Default")
      (node (ref "JP3") (pin "6") (pinfunction "6_6") (pintype "passive"))
      (node (ref "R10") (pin "1") (pinfunction "1_1") (pintype "passive"))
      (node (ref "R2") (pin "1") (pinfunction "1_1") (pintype "passive"))
    )
    (net (code "11") (name "GATE_PI") (class "Default")
      (node (ref "JP1") (pin "1") (pinfunction "1_1") (pintype "passive"))
      (node (ref "R11") (pin "1") (pinfunction "1_1") (pintype "passive"))
    )
    (net (code "12") (name "GATE_SPEC") (class "Default")
      (node (ref "JP3") (pin "10") (pinfunction "10_10") (pintype "passive"))
      (node (ref "R12") (pin "1") (pinfunction "1_1") (pintype "passive"))
    )
    (net (code "13") (name "GND") (class "Default")
      (node (ref "C14") (pin "2") (pinfunction "2_2") (pintype "passive"))
      (node (ref "C17") (pin "2") (pinfunction "2_2") (pintype "passive"))
      (node (ref "C18") (pin "2") (pinfunction "2_2") (pintype "passive"))
      (node (ref "C19") (pin "2") (pinfunction "2_2") (pintype "passive"))
      (node (ref "C2") (pin "1") (pinfunction "1_1") (pintype "passive"))
      (node (ref "C20") (pin "2") (pinfunction "2_2") (pintype "passive"))
      (node (ref "C22") (pin "2") (pinfunction "2_2") (pintype "passive"))
      (node (ref "C23") (pin "2") (pinfunction "2_2") (pintype "passive"))
      (node (ref "C24") (pin "2") (pinfunction "2_2") (pintype "passive"))
      (node (ref "C25") (pin "2") (pinfunction "2_2") (pintype "passive"))
      (node (ref "C26") (pin "2") (pinfunction "2_2") (pintype "passive"))
      (node (ref "C27") (pin "2") (pinfunction "2_2") (pintype "passive"))
      (node (ref "C28") (pin "2") (pinfunction "2_2") (pintype "passive"))
      (node (ref "C29") (pin "2") (pinfunction "2_2") (pintype "passive"))
      (node (ref "C3") (pin "1") (pinfunction "1_1") (pintype "passive"))
      (node (ref "C30") (pin "2") (pinfunction "2_2") (pintype "passive"))
      (node (ref "C7") (pin "1") (pinfunction "1_1") (pintype "passive"))
      (node (ref "C9") (pin "1") (pinfunction "1_1") (pintype "passive"))
      (node (ref "H1") (pin "B2,8") (pinfunction "MOUNT_B2,8") (pintype "passive"))
      (node (ref "H2") (pin "B2,8") (pinfunction "MOUNT_B2,8") (pintype "passive"))
      (node (ref "H3") (pin "B2,8") (pinfunction "MOUNT_B2,8") (pintype "passive"))
      (node (ref "H4") (pin "B2,8") (pinfunction "MOUNT_B2,8") (pintype "passive"))
      (node (ref "H5") (pin "B2,8") (pinfunction "MOUNT_B2,8") (pintype "passive"))
      (node (ref "H6") (pin "B2,8") (pinfunction "MOUNT_B2,8") (pintype "passive"))
      (node (ref "J3") (pin "4") (pinfunction "4_4") (pintype "passive"))
      (node (ref "J5") (pin "1") (pinfunction "1_1") (pintype "passive"))
      (node (ref "J5") (pin "4") (pinfunction "4_4") (pintype "passive"))
      (node (ref "J7") (pin "6") (pinfunction "VSS_6") (pintype "power_in"))
      (node (ref "J7") (pin "G1") (pinfunction "GND_G1") (pintype "power_in"))
      (node (ref "J7") (pin "G2") (pinfunction "GND_G2") (pintype "power_in"))
      (node (ref "J7") (pin "G3") (pinfunction "GND_G3") (pintype "power_in"))
      (node (ref "J7") (pin "G4") (pinfunction "GND_G4") (pintype "power_in"))
      (node (ref "J8") (pin "2") (pinfunction "2_2") (pintype "passive"))
      (node (ref "J8") (pin "4") (pinfunction "4_4") (pintype "passive"))
      (node (ref "J9") (pin "2") (pinfunction "GND_2") (pintype "passive"))
      (node (ref "J9") (pin "3") (pinfunction "GND_3") (pintype "passive"))
      (node (ref "JP1") (pin "13") (pinfunction "13_13") (pintype "passive"))
      (node (ref "JP2") (pin "1") (pinfunction "1_1") (pintype "passive"))
      (node (ref "JP5") (pin "2") (pinfunction "2_2") (pintype "passive"))
      (node (ref "LED1") (pin "C") (pinfunction "C_C") (pintype "passive"))
      (node (ref "LED2") (pin "C") (pinfunction "C_C") (pintype "passive"))
      (node (ref "LED3") (pin "C") (pinfunction "C_C") (pintype "passive"))
      (node (ref "LED4") (pin "C") (pinfunction "C_C") (pintype "passive"))
      (node (ref "R26") (pin "1") (pinfunction "1_1") (pintype "passive"))
      (node (ref "R3") (pin "1") (pinfunction "1_1") (pintype "passive"))
      (node (ref "R32") (pin "1") (pinfunction "1_1") (pintype "passive"))
      (node (ref "R36") (pin "1") (pinfunction "1_1") (pintype "passive"))
      (node (ref "R4") (pin "1") (pinfunction "1_1") (pintype "passive"))
      (node (ref "R40") (pin "1") (pinfunction "1_1") (pintype "passive"))
      (node (ref "SJ3") (pin "3") (pinfunction "3_3") (pintype "passive"))
      (node (ref "SJ5") (pin "1") (pinfunction "1_1") (pintype "passive"))
      (node (ref "SJ7") (pin "1") (pinfunction "1_1") (pintype "passive"))
      (node (ref "U$4") (pin "2") (pinfunction "GND_2") (pintype "bidirectional"))
      (node (ref "U$4") (pin "8") (pinfunction "GND_8") (pintype "bidirectional"))
      (node (ref "U$4") (pin "9") (pinfunction "PS0_WAKEN_9") (pintype "bidirectional"))
      (node (ref "U1") (pin "1") (pinfunction "GND_1") (pintype "power_in"))
      (node (ref "U1") (pin "10") (pinfunction "GND_10") (pintype "power_in"))
      (node (ref "U1") (pin "8") (pinfunction "GND_8") (pintype "power_in"))
      (node (ref "U10") (pin "1") (pinfunction "GND_1") (pintype "power_in"))
      (node (ref "U10") (pin "10") (pinfunction "GND_10") (pintype "power_in"))
      (node (ref "U10") (pin "13") (pinfunction "GND_13") (pintype "power_in"))
      (node (ref "U10") (pin "17") (pinfunction "GND_17") (pintype "power_in"))
      (node (ref "U10") (pin "18") (pinfunction "GND_18") (pintype "power_in"))
      (node (ref "U10") (pin "21") (pinfunction "EXP_21") (pintype "power_in"))
      (node (ref "U10") (pin "22") (pinfunction "EXP_22") (pintype "power_in"))
      (node (ref "U10") (pin "23") (pinfunction "EXP_23") (pintype "power_in"))
      (node (ref "U10") (pin "24") (pinfunction "EXP_24") (pintype "power_in"))
      (node (ref "U10") (pin "25") (pinfunction "EXP_25") (pintype "power_in"))
      (node (ref "U10") (pin "26") (pinfunction "EXP_26") (pintype "power_in"))
      (node (ref "U10") (pin "27") (pinfunction "EXP_27") (pintype "power_in"))
      (node (ref "U10") (pin "28") (pinfunction "EXP_28") (pintype "power_in"))
      (node (ref "U10") (pin "29") (pinfunction "EXP_29") (pintype "power_in"))
      (node (ref "U10") (pin "3") (pinfunction "GND_3") (pintype "power_in"))
      (node (ref "U10") (pin "30") (pinfunction "EXP_30") (pintype "power_in"))
      (node (ref "U10") (pin "5") (pinfunction "GND_5") (pintype "power_in"))
      (node (ref "U10") (pin "6") (pinfunction "GND_6") (pintype "power_in"))
      (node (ref "U10") (pin "7") (pinfunction "GND_7") (pintype "power_in"))
      (node (ref "U10") (pin "9") (pinfunction "GND_9") (pintype "power_in"))
      (node (ref "U11") (pin "15") (pinfunction "GND_15") (pintype "bidirectional"))
      (node (ref "U13") (pin "2") (pinfunction "GND_2") (pintype "power_in"))
      (node (ref "U2") (pin "10") (pinfunction "GND_10") (pintype "power_in"))
      (node (ref "U2") (pin "12") (pinfunction "GND_12") (pintype "power_in"))
      (node (ref "U2") (pin "13") (pinfunction "GND_13") (pintype "power_in"))
      (node (ref "U2") (pin "16") (pinfunction "GND_16") (pintype "power_in"))
      (node (ref "U2") (pin "5") (pinfunction "GND_5") (pintype "power_in"))
      (node (ref "U3") (pin "2") (pinfunction "LED-_2") (pintype "bidirectional"))
      (node (ref "U4") (pin "1") (pinfunction "GND_1") (pintype "power_in"))
      (node (ref "U4") (pin "10") (pinfunction "GND_10") (pintype "power_in"))
      (node (ref "U4") (pin "13") (pinfunction "GND_13") (pintype "power_in"))
      (node (ref "U4") (pin "17") (pinfunction "GND_17") (pintype "power_in"))
      (node (ref "U4") (pin "18") (pinfunction "GND_18") (pintype "power_in"))
      (node (ref "U4") (pin "21") (pinfunction "EXP_21") (pintype "power_in"))
      (node (ref "U4") (pin "22") (pinfunction "EXP_22") (pintype "power_in"))
      (node (ref "U4") (pin "23") (pinfunction "EXP_23") (pintype "power_in"))
      (node (ref "U4") (pin "24") (pinfunction "EXP_24") (pintype "power_in"))
      (node (ref "U4") (pin "25") (pinfunction "EXP_25") (pintype "power_in"))
      (node (ref "U4") (pin "26") (pinfunction "EXP_26") (pintype "power_in"))
      (node (ref "U4") (pin "27") (pinfunction "EXP_27") (pintype "power_in"))
      (node (ref "U4") (pin "28") (pinfunction "EXP_28") (pintype "power_in"))
      (node (ref "U4") (pin "29") (pinfunction "EXP_29") (pintype "power_in"))
      (node (ref "U4") (pin "3") (pinfunction "GND_3") (pintype "power_in"))
      (node (ref "U4") (pin "30") (pinfunction "EXP_30") (pintype "power_in"))
      (node (ref "U4") (pin "5") (pinfunction "GND_5") (pintype "power_in"))
      (node (ref "U4") (pin "6") (pinfunction "GND_6") (pintype "power_in"))
      (node (ref "U4") (pin "7") (pinfunction "GND_7") (pintype "power_in"))
      (node (ref "U4") (pin "9") (pinfunction "GND_9") (pintype "power_in"))
      (node (ref "U5") (pin "1") (pinfunction "GND_1") (pintype "power_in"))
      (node (ref "U5") (pin "10") (pinfunction "GND_10") (pintype "power_in"))
      (node (ref "U5") (pin "13") (pinfunction "GND_13") (pintype "power_in"))
      (node (ref "U5") (pin "17") (pinfunction "GND_17") (pintype "power_in"))
      (node (ref "U5") (pin "18") (pinfunction "GND_18") (pintype "power_in"))
      (node (ref "U5") (pin "21") (pinfunction "EXP_21") (pintype "power_in"))
      (node (ref "U5") (pin "22") (pinfunction "EXP_22") (pintype "power_in"))
      (node (ref "U5") (pin "23") (pinfunction "EXP_23") (pintype "power_in"))
      (node (ref "U5") (pin "24") (pinfunction "EXP_24") (pintype "power_in"))
      (node (ref "U5") (pin "25") (pinfunction "EXP_25") (pintype "power_in"))
      (node (ref "U5") (pin "26") (pinfunction "EXP_26") (pintype "power_in"))
      (node (ref "U5") (pin "27") (pinfunction "EXP_27") (pintype "power_in"))
      (node (ref "U5") (pin "28") (pinfunction "EXP_28") (pintype "power_in"))
      (node (ref "U5") (pin "29") (pinfunction "EXP_29") (pintype "power_in"))
      (node (ref "U5") (pin "3") (pinfunction "GND_3") (pintype "power_in"))
      (node (ref "U5") (pin "30") (pinfunction "EXP_30") (pintype "power_in"))
      (node (ref "U5") (pin "5") (pinfunction "GND_5") (pintype "power_in"))
      (node (ref "U5") (pin "6") (pinfunction "GND_6") (pintype "power_in"))
      (node (ref "U5") (pin "7") (pinfunction "GND_7") (pintype "power_in"))
      (node (ref "U5") (pin "9") (pinfunction "GND_9") (pintype "power_in"))
      (node (ref "U6") (pin "6") (pinfunction "GND_6") (pintype "power_in"))
      (node (ref "U6") (pin "7") (pinfunction "FSYNC_7") (pintype "input"))
      (node (ref "U7") (pin "1") (pinfunction "GND_1") (pintype "power_in"))
      (node (ref "U7") (pin "10") (pinfunction "GND_10") (pintype "power_in"))
      (node (ref "U7") (pin "13") (pinfunction "GND_13") (pintype "power_in"))
      (node (ref "U7") (pin "17") (pinfunction "GND_17") (pintype "power_in"))
      (node (ref "U7") (pin "18") (pinfunction "GND_18") (pintype "power_in"))
      (node (ref "U7") (pin "21") (pinfunction "EXP_21") (pintype "power_in"))
      (node (ref "U7") (pin "22") (pinfunction "EXP_22") (pintype "power_in"))
      (node (ref "U7") (pin "23") (pinfunction "EXP_23") (pintype "power_in"))
      (node (ref "U7") (pin "24") (pinfunction "EXP_24") (pintype "power_in"))
      (node (ref "U7") (pin "25") (pinfunction "EXP_25") (pintype "power_in"))
      (node (ref "U7") (pin "26") (pinfunction "EXP_26") (pintype "power_in"))
      (node (ref "U7") (pin "27") (pinfunction "EXP_27") (pintype "power_in"))
      (node (ref "U7") (pin "28") (pinfunction "EXP_28") (pintype "power_in"))
      (node (ref "U7") (pin "29") (pinfunction "EXP_29") (pintype "power_in"))
      (node (ref "U7") (pin "3") (pinfunction "GND_3") (pintype "power_in"))
      (node (ref "U7") (pin "30") (pinfunction "EXP_30") (pintype "power_in"))
      (node (ref "U7") (pin "5") (pinfunction "GND_5") (pintype "power_in"))
      (node (ref "U7") (pin "6") (pinfunction "GND_6") (pintype "power_in"))
      (node (ref "U7") (pin "7") (pinfunction "GND_7") (pintype "power_in"))
      (node (ref "U7") (pin "9") (pinfunction "GND_9") (pintype "power_in"))
      (node (ref "U8") (pin "1") (pinfunction "GND_1") (pintype "power_in"))
      (node (ref "U8") (pin "10") (pinfunction "GND_10") (pintype "power_in"))
      (node (ref "U8") (pin "13") (pinfunction "GND_13") (pintype "power_in"))
      (node (ref "U8") (pin "17") (pinfunction "GND_17") (pintype "power_in"))
      (node (ref "U8") (pin "18") (pinfunction "GND_18") (pintype "power_in"))
      (node (ref "U8") (pin "21") (pinfunction "EXP_21") (pintype "power_in"))
      (node (ref "U8") (pin "22") (pinfunction "EXP_22") (pintype "power_in"))
      (node (ref "U8") (pin "23") (pinfunction "EXP_23") (pintype "power_in"))
      (node (ref "U8") (pin "24") (pinfunction "EXP_24") (pintype "power_in"))
      (node (ref "U8") (pin "25") (pinfunction "EXP_25") (pintype "power_in"))
      (node (ref "U8") (pin "26") (pinfunction "EXP_26") (pintype "power_in"))
      (node (ref "U8") (pin "27") (pinfunction "EXP_27") (pintype "power_in"))
      (node (ref "U8") (pin "28") (pinfunction "EXP_28") (pintype "power_in"))
      (node (ref "U8") (pin "29") (pinfunction "EXP_29") (pintype "power_in"))
      (node (ref "U8") (pin "3") (pinfunction "GND_3") (pintype "power_in"))
      (node (ref "U8") (pin "30") (pinfunction "EXP_30") (pintype "power_in"))
      (node (ref "U8") (pin "5") (pinfunction "GND_5") (pintype "power_in"))
      (node (ref "U8") (pin "6") (pinfunction "GND_6") (pintype "power_in"))
      (node (ref "U8") (pin "7") (pinfunction "GND_7") (pintype "power_in"))
      (node (ref "U8") (pin "9") (pinfunction "GND_9") (pintype "power_in"))
      (node (ref "U9") (pin "1") (pinfunction "GND_1") (pintype "power_in"))
      (node (ref "U9") (pin "10") (pinfunction "GND_10") (pintype "power_in"))
      (node (ref "U9") (pin "13") (pinfunction "GND_13") (pintype "power_in"))
      (node (ref "U9") (pin "17") (pinfunction "GND_17") (pintype "power_in"))
      (node (ref "U9") (pin "18") (pinfunction "GND_18") (pintype "power_in"))
      (node (ref "U9") (pin "21") (pinfunction "EXP_21") (pintype "power_in"))
      (node (ref "U9") (pin "22") (pinfunction "EXP_22") (pintype "power_in"))
      (node (ref "U9") (pin "23") (pinfunction "EXP_23") (pintype "power_in"))
      (node (ref "U9") (pin "24") (pinfunction "EXP_24") (pintype "power_in"))
      (node (ref "U9") (pin "25") (pinfunction "EXP_25") (pintype "power_in"))
      (node (ref "U9") (pin "26") (pinfunction "EXP_26") (pintype "power_in"))
      (node (ref "U9") (pin "27") (pinfunction "EXP_27") (pintype "power_in"))
      (node (ref "U9") (pin "28") (pinfunction "EXP_28") (pintype "power_in"))
      (node (ref "U9") (pin "29") (pinfunction "EXP_29") (pintype "power_in"))
      (node (ref "U9") (pin "3") (pinfunction "GND_3") (pintype "power_in"))
      (node (ref "U9") (pin "30") (pinfunction "EXP_30") (pintype "power_in"))
      (node (ref "U9") (pin "5") (pinfunction "GND_5") (pintype "power_in"))
      (node (ref "U9") (pin "6") (pinfunction "GND_6") (pintype "power_in"))
      (node (ref "U9") (pin "7") (pinfunction "GND_7") (pintype "power_in"))
      (node (ref "U9") (pin "9") (pinfunction "GND_9") (pintype "power_in"))
    )
    (net (code "14") (name "GND_IRIDIUM") (class "Default")
      (node (ref "J2") (pin "4") (pinfunction "4_4") (pintype "passive"))
      (node (ref "J4") (pin "4") (pinfunction "4_4") (pintype "passive"))
    )
    (net (code "15") (name "GND_PI") (class "Default")
      (node (ref "J1") (pin "4") (pinfunction "4_4") (pintype "passive"))
    )
    (net (code "16") (name "GND_SPEC") (class "Default")
      (node (ref "J6") (pin "4") (pinfunction "4_4") (pintype "passive"))
    )
    (net (code "17") (name "H3_INT1") (class "Default")
      (node (ref "JP7") (pin "2") (pinfunction "2_2") (pintype "passive"))
      (node (ref "U2") (pin "11") (pinfunction "INT1_11") (pintype "output"))
    )
    (net (code "18") (name "H3_INT2") (class "Default")
      (node (ref "JP7") (pin "3") (pinfunction "3_3") (pintype "passive"))
      (node (ref "U2") (pin "9") (pinfunction "INT2_9") (pintype "output"))
    )
    (net (code "19") (name "HINTN") (class "Default")
      (node (ref "JP6") (pin "4") (pinfunction "4_4") (pintype "passive"))
      (node (ref "U$4") (pin "5") (pinfunction "HINTN_5") (pintype "bidirectional"))
    )
    (net (code "20") (name "ICM_INT") (class "Default")
      (node (ref "JP7") (pin "1") (pinfunction "1_1") (pintype "passive"))
      (node (ref "U6") (pin "4") (pinfunction "INT1/INT_4") (pintype "output"))
    )
    (net (code "21") (name "MISO") (class "Default")
      (node (ref "J7") (pin "7") (pinfunction "DAT0_7") (pintype "bidirectional"))
      (node (ref "JP1") (pin "4") (pinfunction "4_4") (pintype "passive"))
      (node (ref "U1") (pin "2") (pinfunction "MISO_2") (pintype "input"))
    )
    (net (code "22") (name "MOSI") (class "Default")
      (node (ref "J7") (pin "3") (pinfunction "CMD_3") (pintype "bidirectional"))
      (node (ref "JP1") (pin "5") (pinfunction "5_5") (pintype "passive"))
      (node (ref "U1") (pin "3") (pinfunction "MOSI_3") (pintype "output"))
    )
    (net (code "23") (name "Net-(H7-MOUNT)") (class "Default")
      (node (ref "H7") (pin "B2,8") (pinfunction "MOUNT_B2,8") (pintype "passive"))
      (node (ref "R17") (pin "1") (pinfunction "1_1") (pintype "passive"))
    )
    (net (code "24") (name "Net-(H8-MOUNT)") (class "Default")
      (node (ref "H8") (pin "B2,8") (pinfunction "MOUNT_B2,8") (pintype "passive"))
      (node (ref "R18") (pin "1") (pinfunction "1_1") (pintype "passive"))
    )
    (net (code "25") (name "Net-(H9-MOUNT)") (class "Default")
      (node (ref "H9") (pin "B2,8") (pinfunction "MOUNT_B2,8") (pintype "passive"))
      (node (ref "R13") (pin "1") (pinfunction "1_1") (pintype "passive"))
    )
    (net (code "26") (name "Net-(H10-MOUNT)") (class "Default")
      (node (ref "H10") (pin "B2,8") (pinfunction "MOUNT_B2,8") (pintype "passive"))
      (node (ref "R14") (pin "1") (pinfunction "1_1") (pintype "passive"))
    )
    (net (code "27") (name "Net-(H11-MOUNT)") (class "Default")
      (node (ref "H11") (pin "B2,8") (pinfunction "MOUNT_B2,8") (pintype "passive"))
      (node (ref "R20") (pin "1") (pinfunction "1_1") (pintype "passive"))
    )
    (net (code "28") (name "Net-(H12-MOUNT)") (class "Default")
      (node (ref "H12") (pin "B2,8") (pinfunction "MOUNT_B2,8") (pintype "passive"))
      (node (ref "R19") (pin "1") (pinfunction "1_1") (pintype "passive"))
    )
    (net (code "29") (name "Net-(H13-MOUNT)") (class "Default")
      (node (ref "H13") (pin "B2,8") (pinfunction "MOUNT_B2,8") (pintype "passive"))
      (node (ref "R22") (pin "1") (pinfunction "1_1") (pintype "passive"))
    )
    (net (code "30") (name "Net-(H14-MOUNT)") (class "Default")
      (node (ref "H14") (pin "B2,8") (pinfunction "MOUNT_B2,8") (pintype "passive"))
      (node (ref "R21") (pin "1") (pinfunction "1_1") (pintype "passive"))
    )
    (net (code "31") (name "Net-(H15-MOUNT)") (class "Default")
      (node (ref "H15") (pin "B2,8") (pinfunction "MOUNT_B2,8") (pintype "passive"))
      (node (ref "R23") (pin "1") (pinfunction "1_1") (pintype "passive"))
    )
    (net (code "32") (name "Net-(H16-MOUNT)") (class "Default")
      (node (ref "H16") (pin "B2,8") (pinfunction "MOUNT_B2,8") (pintype "passive"))
      (node (ref "R24") (pin "1") (pinfunction "1_1") (pintype "passive"))
    )
    (net (code "33") (name "Net-(H17-MOUNT)") (class "Default")
      (node (ref "H17") (pin "B2,8") (pinfunction "MOUNT_B2,8") (pintype "passive"))
      (node (ref "R15") (pin "1") (pinfunction "1_1") (pintype "passive"))
    )
    (net (code "34") (name "Net-(H18-MOUNT)") (class "Default")
      (node (ref "H18") (pin "B2,8") (pinfunction "MOUNT_B2,8") (pintype "passive"))
      (node (ref "R16") (pin "1") (pinfunction "1_1") (pintype "passive"))
    )
    (net (code "35") (name "Net-(J2-Pad1)") (class "Default")
      (node (ref "J2") (pin "1") (pinfunction "1_1") (pintype "passive"))
      (node (ref "SJ2") (pin "2") (pinfunction "2_2") (pintype "passive"))
    )
    (net (code "36") (name "Net-(J2-Pad2)") (class "Default")
      (node (ref "J2") (pin "2") (pinfunction "2_2") (pintype "passive"))
      (node (ref "SJ1") (pin "2") (pinfunction "2_2") (pintype "passive"))
    )
    (net (code "37") (name "Net-(J2-Pad3)") (class "Default")
      (node (ref "J2") (pin "3") (pinfunction "3_3") (pintype "passive"))
      (node (ref "SJ10") (pin "2") (pinfunction "2_2") (pintype "passive"))
    )
    (net (code "38") (name "Net-(J4-Pad3)") (class "Default")
      (node (ref "J4") (pin "3") (pinfunction "3_3") (pintype "passive"))
      (node (ref "SJ11") (pin "2") (pinfunction "2_2") (pintype "passive"))
    )
    (net (code "39") (name "Net-(J9-SIG)") (class "Default")
      (node (ref "J9") (pin "1") (pinfunction "SIG_1") (pintype "passive"))
      (node (ref "U1") (pin "9") (pinfunction "ANT_9") (pintype "bidirectional"))
    )
    (net (code "40") (name "Net-(LED1-PadA)") (class "Default")
      (node (ref "LED1") (pin "A") (pinfunction "A_A") (pintype "passive"))
      (node (ref "R10") (pin "2") (pinfunction "2_2") (pintype "passive"))
    )
    (net (code "41") (name "Net-(LED2-PadA)") (class "Default")
      (node (ref "LED2") (pin "A") (pinfunction "A_A") (pintype "passive"))
      (node (ref "R11") (pin "2") (pinfunction "2_2") (pintype "passive"))
    )
    (net (code "42") (name "Net-(LED3-PadA)") (class "Default")
      (node (ref "LED3") (pin "A") (pinfunction "A_A") (pintype "passive"))
      (node (ref "R12") (pin "2") (pinfunction "2_2") (pintype "passive"))
    )
    (net (code "43") (name "Net-(LED4-PadA)") (class "Default")
      (node (ref "LED4") (pin "A") (pinfunction "A_A") (pintype "passive"))
      (node (ref "R27") (pin "2") (pinfunction "2_2") (pintype "passive"))
    )
    (net (code "44") (name "Net-(U$4-SA0)") (class "Default")
      (node (ref "SJ3") (pin "2") (pinfunction "2_2") (pintype "passive"))
      (node (ref "U$4") (pin "14") (pinfunction "SA0_14") (pintype "bidirectional"))
    )
    (net (code "45") (name "Net-(U1-3.3V)") (class "Default")
      (node (ref "JP4") (pin "1") (pinfunction "1_1") (pintype "passive"))
      (node (ref "SJ9") (pin "1") (pinfunction "1_1") (pintype "passive"))
      (node (ref "U1") (pin "13") (pinfunction "3.3V_13") (pintype "power_in"))
    )
    (net (code "46") (name "Net-(U2-SDO{slash}SA0)") (class "Default")
      (node (ref "SJ7") (pin "2") (pinfunction "2_2") (pintype "passive"))
      (node (ref "U2") (pin "7") (pinfunction "SDO/SA0_7") (pintype "bidirectional"))
    )
    (net (code "47") (name "Net-(U3-LED+)") (class "Default")
      (node (ref "C3") (pin "2") (pinfunction "2_2") (pintype "passive"))
      (node (ref "R2") (pin "2") (pinfunction "2_2") (pintype "passive"))
      (node (ref "U3") (pin "1") (pinfunction "LED+_1") (pintype "bidirectional"))
    )
    (net (code "48") (name "Net-(U4-ADDR)") (class "Default")
      (node (ref "R35") (pin "2") (pinfunction "2_2") (pintype "passive"))
      (node (ref "R36") (pin "2") (pinfunction "2_2") (pintype "passive"))
      (node (ref "U4") (pin "16") (pinfunction "ADDR_16") (pintype "input"))
    )
    (net (code "49") (name "Net-(U4-VIN+)") (class "Default")
      (node (ref "C10") (pin "1") (pinfunction "1_1") (pintype "passive"))
      (node (ref "R13") (pin "2") (pinfunction "2_2") (pintype "passive"))
      (node (ref "U4") (pin "2") (pinfunction "VIN+_2") (pintype "input"))
    )
    (net (code "50") (name "Net-(U4-VIN-)") (class "Default")
      (node (ref "C10") (pin "2") (pinfunction "2_2") (pintype "passive"))
      (node (ref "R14") (pin "2") (pinfunction "2_2") (pintype "passive"))
      (node (ref "U4") (pin "4") (pinfunction "VIN-_4") (pintype "input"))
    )
    (net (code "51") (name "Net-(U5-ADDR)") (class "Default")
      (node (ref "R25") (pin "2") (pinfunction "2_2") (pintype "passive"))
      (node (ref "R26") (pin "2") (pinfunction "2_2") (pintype "passive"))
      (node (ref "U5") (pin "16") (pinfunction "ADDR_16") (pintype "input"))
    )
    (net (code "52") (name "Net-(U5-VIN+)") (class "Default")
      (node (ref "C11") (pin "1") (pinfunction "1_1") (pintype "passive"))
      (node (ref "R15") (pin "2") (pinfunction "2_2") (pintype "passive"))
      (node (ref "U5") (pin "2") (pinfunction "VIN+_2") (pintype "input"))
    )
    (net (code "53") (name "Net-(U5-VIN-)") (class "Default")
      (node (ref "C11") (pin "2") (pinfunction "2_2") (pintype "passive"))
      (node (ref "R16") (pin "2") (pinfunction "2_2") (pintype "passive"))
      (node (ref "U5") (pin "4") (pinfunction "VIN-_4") (pintype "input"))
    )
    (net (code "54") (name "Net-(U6-AP_SDO{slash}AP_AD0)") (class "Default")
      (node (ref "SJ5") (pin "2") (pinfunction "2_2") (pintype "passive"))
      (node (ref "U6") (pin "1") (pinfunction "AP_SDO/AP_AD0_1") (pintype "bidirectional"))
    )
    (net (code "55") (name "Net-(U7-ADDR)") (class "Default")
      (node (ref "R4") (pin "2") (pinfunction "2_2") (pintype "passive"))
      (node (ref "R9") (pin "2") (pinfunction "2_2") (pintype "passive"))
      (node (ref "U7") (pin "16") (pinfunction "ADDR_16") (pintype "input"))
    )
    (net (code "56") (name "Net-(U7-VIN+)") (class "Default")
      (node (ref "C12") (pin "1") (pinfunction "1_1") (pintype "passive"))
      (node (ref "R20") (pin "2") (pinfunction "2_2") (pintype "passive"))
      (node (ref "U7") (pin "2") (pinfunction "VIN+_2") (pintype "input"))
    )
    (net (code "57") (name "Net-(U7-VIN-)") (class "Default")
      (node (ref "C12") (pin "2") (pinfunction "2_2") (pintype "passive"))
      (node (ref "R19") (pin "2") (pinfunction "2_2") (pintype "passive"))
      (node (ref "U7") (pin "4") (pinfunction "VIN-_4") (pintype "input"))
    )
    (net (code "58") (name "Net-(U8-ADDR)") (class "Default")
      (node (ref "R1") (pin "2") (pinfunction "2_2") (pintype "passive"))
      (node (ref "R3") (pin "2") (pinfunction "2_2") (pintype "passive"))
      (node (ref "U8") (pin "16") (pinfunction "ADDR_16") (pintype "input"))
    )
    (net (code "59") (name "Net-(U8-VIN+)") (class "Default")
      (node (ref "C15") (pin "1") (pinfunction "1_1") (pintype "passive"))
      (node (ref "R23") (pin "2") (pinfunction "2_2") (pintype "passive"))
      (node (ref "U8") (pin "2") (pinfunction "VIN+_2") (pintype "input"))
    )
    (net (code "60") (name "Net-(U8-VIN-)") (class "Default")
      (node (ref "C15") (pin "2") (pinfunction "2_2") (pintype "passive"))
      (node (ref "R24") (pin "2") (pinfunction "2_2") (pintype "passive"))
      (node (ref "U8") (pin "4") (pinfunction "VIN-_4") (pintype "input"))
    )
    (net (code "61") (name "Net-(U9-ADDR)") (class "Default")
      (node (ref "R31") (pin "2") (pinfunction "2_2") (pintype "passive"))
      (node (ref "R32") (pin "2") (pinfunction "2_2") (pintype "passive"))
      (node (ref "U9") (pin "16") (pinfunction "ADDR_16") (pintype "input"))
    )
    (net (code "62") (name "Net-(U9-VIN+)") (class "Default")
      (node (ref "C13") (pin "1") (pinfunction "1_1") (pintype "passive"))
      (node (ref "R17") (pin "2") (pinfunction "2_2") (pintype "passive"))
      (node (ref "U9") (pin "2") (pinfunction "VIN+_2") (pintype "input"))
    )
    (net (code "63") (name "Net-(U9-VIN-)") (class "Default")
      (node (ref "C13") (pin "2") (pinfunction "2_2") (pintype "passive"))
      (node (ref "R18") (pin "2") (pinfunction "2_2") (pintype "passive"))
      (node (ref "U9") (pin "4") (pinfunction "VIN-_4") (pintype "input"))
    )
    (net (code "64") (name "Net-(U10-ADDR)") (class "Default")
      (node (ref "R39") (pin "2") (pinfunction "2_2") (pintype "passive"))
      (node (ref "R40") (pin "2") (pinfunction "2_2") (pintype "passive"))
      (node (ref "U10") (pin "16") (pinfunction "ADDR_16") (pintype "input"))
    )
    (net (code "65") (name "Net-(U10-VIN+)") (class "Default")
      (node (ref "C1") (pin "1") (pinfunction "1_1") (pintype "passive"))
      (node (ref "R22") (pin "2") (pinfunction "2_2") (pintype "passive"))
      (node (ref "U10") (pin "2") (pinfunction "VIN+_2") (pintype "input"))
    )
    (net (code "66") (name "Net-(U10-VIN-)") (class "Default")
      (node (ref "C1") (pin "2") (pinfunction "2_2") (pintype "passive"))
      (node (ref "R21") (pin "2") (pinfunction "2_2") (pintype "passive"))
      (node (ref "U10") (pin "4") (pinfunction "VIN-_4") (pintype "input"))
    )
    (net (code "67") (name "Net-(U11-C1+)") (class "Default")
      (node (ref "C6") (pin "2") (pinfunction "2_2") (pintype "passive"))
      (node (ref "U11") (pin "1") (pinfunction "C1+_1") (pintype "bidirectional"))
    )
    (net (code "68") (name "Net-(U11-C1-)") (class "Default")
      (node (ref "C6") (pin "1") (pinfunction "1_1") (pintype "passive"))
      (node (ref "U11") (pin "3") (pinfunction "C1-_3") (pintype "bidirectional"))
    )
    (net (code "69") (name "Net-(U11-C2+)") (class "Default")
      (node (ref "C8") (pin "2") (pinfunction "2_2") (pintype "passive"))
      (node (ref "U11") (pin "4") (pinfunction "C2+_4") (pintype "bidirectional"))
    )
    (net (code "70") (name "Net-(U11-C2-)") (class "Default")
      (node (ref "C8") (pin "1") (pinfunction "1_1") (pintype "passive"))
      (node (ref "U11") (pin "5") (pinfunction "C2-_5") (pintype "bidirectional"))
    )
    (net (code "71") (name "Net-(U11-V+)") (class "Default")
      (node (ref "C7") (pin "2") (pinfunction "2_2") (pintype "passive"))
      (node (ref "U11") (pin "2") (pinfunction "V+_2") (pintype "bidirectional"))
    )
    (net (code "72") (name "Net-(U11-V-)") (class "Default")
      (node (ref "C9") (pin "2") (pinfunction "2_2") (pintype "passive"))
      (node (ref "U11") (pin "6") (pinfunction "V-_6") (pintype "bidirectional"))
    )
    (net (code "73") (name "Net-(U11-VCC)") (class "Default")
      (node (ref "C2") (pin "2") (pinfunction "2_2") (pintype "passive"))
      (node (ref "SJ8") (pin "2") (pinfunction "2_2") (pintype "passive"))
      (node (ref "U11") (pin "16") (pinfunction "VCC_16") (pintype "bidirectional"))
    )
    (net (code "74") (name "Net-(U13-IN)") (class "Default")
      (node (ref "C22") (pin "1") (pinfunction "1_1") (pintype "passive"))
      (node (ref "R45") (pin "1") (pinfunction "1_1") (pintype "passive"))
      (node (ref "SJ6") (pin "2") (pinfunction "2_2") (pintype "passive"))
      (node (ref "U13") (pin "1") (pinfunction "IN_1") (pintype "power_in"))
    )
    (net (code "75") (name "PS1") (class "Default")
      (node (ref "JP6") (pin "2") (pinfunction "2_2") (pintype "passive"))
      (node (ref "U$4") (pin "7") (pinfunction "PS1_7") (pintype "bidirectional"))
    )
    (net (code "76") (name "R232") (class "Default")
      (node (ref "J4") (pin "2") (pinfunction "2_2") (pintype "passive"))
      (node (ref "U11") (pin "8") (pinfunction "R1IN_8") (pintype "bidirectional"))
    )
    (net (code "77") (name "R232_GPS") (class "Default")
      (node (ref "SJ1") (pin "1") (pinfunction "1_1") (pintype "passive"))
      (node (ref "U11") (pin "13") (pinfunction "R2IN_13") (pintype "bidirectional"))
    )
    (net (code "78") (name "RADIO_RESET") (class "Default")
      (node (ref "JP3") (pin "8") (pinfunction "8_8") (pintype "passive"))
      (node (ref "U1") (pin "6") (pinfunction "RESET_6") (pintype "bidirectional"))
    )
    (net (code "79") (name "RADIO_SS") (class "Default")
      (node (ref "JP3") (pin "7") (pinfunction "7_7") (pintype "passive"))
      (node (ref "U1") (pin "5") (pinfunction "NSS_5") (pintype "input"))
    )
    (net (code "80") (name "RGPS") (class "Default")
      (node (ref "JP1") (pin "9") (pinfunction "9_9") (pintype "passive"))
      (node (ref "SJ1") (pin "3") (pinfunction "3_3") (pintype "passive"))
      (node (ref "U11") (pin "12") (pinfunction "R2OUT_12") (pintype "bidirectional"))
    )
    (net (code "81") (name "RIRI") (class "Default")
      (node (ref "JP3") (pin "4") (pinfunction "4_4") (pintype "passive"))
      (node (ref "U11") (pin "9") (pinfunction "R1OUT_9") (pintype "bidirectional"))
    )
    (net (code "82") (name "RX1") (class "Default")
      (node (ref "J1") (pin "1") (pinfunction "1_1") (pintype "passive"))
      (node (ref "JP1") (pin "3") (pinfunction "3_3") (pintype "passive"))
    )
    (net (code "83") (name "RX4") (class "Default")
      (node (ref "J6") (pin "1") (pinfunction "1_1") (pintype "passive"))
      (node (ref "JP1") (pin "11") (pinfunction "11_11") (pintype "passive"))
    )
    (net (code "84") (name "SCK") (class "Default")
      (node (ref "J7") (pin "5") (pinfunction "CLK_5") (pintype "input"))
      (node (ref "JP1") (pin "6") (pinfunction "6_6") (pintype "passive"))
      (node (ref "U1") (pin "4") (pinfunction "SCK_4") (pintype "input"))
    )
    (net (code "85") (name "SCL") (class "Default")
      (node (ref "J3") (pin "1") (pinfunction "1_1") (pintype "passive"))
      (node (ref "JP3") (pin "11") (pinfunction "11_11") (pintype "passive"))
      (node (ref "R8") (pin "2") (pinfunction "2_2") (pintype "passive"))
      (node (ref "U$4") (pin "12") (pinfunction "SCL_12") (pintype "bidirectional"))
      (node (ref "U10") (pin "19") (pinfunction "SCL_19") (pintype "input"))
      (node (ref "U2") (pin "4") (pinfunction "SCL/SPC_4") (pintype "input"))
      (node (ref "U4") (pin "19") (pinfunction "SCL_19") (pintype "input"))
      (node (ref "U5") (pin "19") (pinfunction "SCL_19") (pintype "input"))
      (node (ref "U6") (pin "13") (pinfunction "AP_SCL/AP_SCLK_13") (pintype "input"))
      (node (ref "U7") (pin "19") (pinfunction "SCL_19") (pintype "input"))
      (node (ref "U8") (pin "19") (pinfunction "SCL_19") (pintype "input"))
      (node (ref "U9") (pin "19") (pinfunction "SCL_19") (pintype "input"))
    )
    (net (code "86") (name "SDA") (class "Default")
      (node (ref "J3") (pin "2") (pinfunction "2_2") (pintype "passive"))
      (node (ref "JP3") (pin "12") (pinfunction "12_12") (pintype "passive"))
      (node (ref "R7") (pin "2") (pinfunction "2_2") (pintype "passive"))
      (node (ref "U$4") (pin "11") (pinfunction "SDA_11") (pintype "bidirectional"))
      (node (ref "U10") (pin "20") (pinfunction "SDA_20") (pintype "bidirectional"))
      (node (ref "U2") (pin "6") (pinfunction "SDA/SDI/SDO_6") (pintype "bidirectional"))
      (node (ref "U4") (pin "20") (pinfunction "SDA_20") (pintype "bidirectional"))
      (node (ref "U5") (pin "20") (pinfunction "SDA_20") (pintype "bidirectional"))
      (node (ref "U6") (pin "14") (pinfunction "AP_SDA/AP_SDIO/AP_SDI_14") (pintype "bidirectional"))
      (node (ref "U7") (pin "20") (pinfunction "SDA_20") (pintype "bidirectional"))
      (node (ref "U8") (pin "20") (pinfunction "SDA_20") (pintype "bidirectional"))
      (node (ref "U9") (pin "20") (pinfunction "SDA_20") (pintype "bidirectional"))
    )
    (net (code "87") (name "SD_CS") (class "Default")
      (node (ref "J7") (pin "2") (pinfunction "CD/DAT3_2") (pintype "bidirectional"))
      (node (ref "JP1") (pin "7") (pinfunction "7_7") (pintype "passive"))
    )
    (net (code "88") (name "T232") (class "Default")
      (node (ref "J4") (pin "1") (pinfunction "1_1") (pintype "passive"))
      (node (ref "U11") (pin "7") (pinfunction "T1OUT_7") (pintype "bidirectional"))
    )
    (net (code "89") (name "T232_GPS") (class "Default")
      (node (ref "SJ2") (pin "1") (pinfunction "1_1") (pintype "passive"))
      (node (ref "U11") (pin "14") (pinfunction "T2OUT_14") (pintype "bidirectional"))
    )
    (net (code "90") (name "TGPS") (class "Default")
      (node (ref "JP1") (pin "10") (pinfunction "10_10") (pintype "passive"))
      (node (ref "SJ2") (pin "3") (pinfunction "3_3") (pintype "passive"))
      (node (ref "U11") (pin "11") (pinfunction "T2IN_11") (pintype "bidirectional"))
    )
    (net (code "91") (name "TIRI") (class "Default")
      (node (ref "JP3") (pin "5") (pinfunction "5_5") (pintype "passive"))
      (node (ref "U11") (pin "10") (pinfunction "T1IN_10") (pintype "bidirectional"))
    )
    (net (code "92") (name "TX1") (class "Default")
      (node (ref "J1") (pin "2") (pinfunction "2_2") (pintype "passive"))
      (node (ref "JP1") (pin "2") (pinfunction "2_2") (pintype "passive"))
    )
    (net (code "93") (name "TX4") (class "Default")
      (node (ref "J6") (pin "2") (pinfunction "2_2") (pintype "passive"))
      (node (ref "JP1") (pin "8") (pinfunction "8_8") (pintype "passive"))
    )
    (net (code "94") (name "VBAT") (class "Default")
      (node (ref "J5") (pin "3") (pinfunction "3_3") (pintype "passive"))
      (node (ref "JP2") (pin "3") (pinfunction "3_3") (pintype "passive"))
      (node (ref "JP3") (pin "1") (pinfunction "1_1") (pintype "passive"))
      (node (ref "SJ6") (pin "3") (pinfunction "3_3") (pintype "passive"))
    )
    (net (code "95") (name "VBUS") (class "Default")
      (node (ref "JP3") (pin "3") (pinfunction "3_3") (pintype "passive"))
      (node (ref "SJ4") (pin "2") (pinfunction "2_2") (pintype "passive"))
    )
    (net (code "96") (name "VIN") (class "Default")
      (node (ref "J8") (pin "3") (pinfunction "3_3") (pintype "passive"))
      (node (ref "JP2") (pin "2") (pinfunction "2_2") (pintype "passive"))
      (node (ref "SJ10") (pin "1") (pinfunction "1_1") (pintype "passive"))
      (node (ref "SJ11") (pin "1") (pinfunction "1_1") (pintype "passive"))
      (node (ref "U3") (pin "4") (pinfunction "SW+2_4") (pintype "bidirectional"))
    )
    (net (code "97") (name "VIN_PRE") (class "Default")
      (node (ref "J5") (pin "2") (pinfunction "2_2") (pintype "passive"))
      (node (ref "U3") (pin "6") (pinfunction "SW+1_6") (pintype "bidirectional"))
    )
    (net (code "98") (name "unconnected-(J7-DAT1-Pad8)") (class "Default")
      (node (ref "J7") (pin "8") (pinfunction "DAT1_8") (pintype "bidirectional"))
    )
    (net (code "99") (name "unconnected-(J7-DAT2-Pad1)") (class "Default")
      (node (ref "J7") (pin "1") (pinfunction "DAT2_1") (pintype "bidirectional"))
    )
    (net (code "100") (name "unconnected-(J7-SW-1-Pad9)") (class "Default")
      (node (ref "J7") (pin "9") (pinfunction "SW-1_9") (pintype "passive"))
    )
    (net (code "101") (name "unconnected-(J7-SW-2-Pad10)") (class "Default")
      (node (ref "J7") (pin "10") (pinfunction "SW-2_10") (pintype "passive"))
    )
    (net (code "102") (name "unconnected-(JP3-Pad2)") (class "Default")
      (node (ref "JP3") (pin "2") (pinfunction "2_2") (pintype "passive"))
    )
    (net (code "103") (name "unconnected-(U$4-CSN-Pad15)") (class "Default")
      (node (ref "U$4") (pin "15") (pinfunction "CSN_15") (pintype "bidirectional"))
    )
    (net (code "104") (name "unconnected-(U1-DIO1-Pad15)") (class "Default")
      (node (ref "U1") (pin "15") (pinfunction "DIO1_15") (pintype "bidirectional"))
    )
    (net (code "105") (name "unconnected-(U1-DIO2-Pad16)") (class "Default")
      (node (ref "U1") (pin "16") (pinfunction "DIO2_16") (pintype "bidirectional"))
    )
    (net (code "106") (name "unconnected-(U1-DIO3-Pad11)") (class "Default")
      (node (ref "U1") (pin "11") (pinfunction "DIO3_11") (pintype "bidirectional"))
    )
    (net (code "107") (name "unconnected-(U1-DIO4-Pad12)") (class "Default")
      (node (ref "U1") (pin "12") (pinfunction "DIO4_12") (pintype "bidirectional"))
    )
    (net (code "108") (name "unconnected-(U1-DIO5-Pad7)") (class "Default")
      (node (ref "U1") (pin "7") (pinfunction "DIO5_7") (pintype "bidirectional"))
    )
    (net (code "109") (name "unconnected-(U2-NC-Pad2)") (class "Default")
      (node (ref "U2") (pin "2") (pinfunction "NC_2") (pintype "no_connect"))
    )
    (net (code "110") (name "unconnected-(U2-NC-Pad3)") (class "Default")
      (node (ref "U2") (pin "3") (pinfunction "NC_3") (pintype "no_connect"))
    )
    (net (code "111") (name "unconnected-(U3-N{slash}C-Pad3)") (class "Default")
      (node (ref "U3") (pin "3") (pinfunction "N/C_3") (pintype "no_connect"))
    )
    (net (code "112") (name "unconnected-(U3-SW--Pad5)") (class "Default")
      (node (ref "U3") (pin "5") (pinfunction "SW-_5") (pintype "bidirectional"))
    )
    (net (code "113") (name "unconnected-(U4-ALERT_1-Pad11)") (class "Default")
      (node (ref "U4") (pin "11") (pinfunction "ALERT_1_11") (pintype "output"))
    )
    (net (code "114") (name "unconnected-(U4-ALERT_2-Pad12)") (class "Default")
      (node (ref "U4") (pin "12") (pinfunction "ALERT_2_12") (pintype "output"))
    )
    (net (code "115") (name "unconnected-(U4-ALERT_3-Pad14)") (class "Default")
      (node (ref "U4") (pin "14") (pinfunction "ALERT_3_14") (pintype "output"))
    )
    (net (code "116") (name "unconnected-(U4-ALERT_4-Pad15)") (class "Default")
      (node (ref "U4") (pin "15") (pinfunction "ALERT_4_15") (pintype "output"))
    )
    (net (code "117") (name "unconnected-(U5-ALERT_1-Pad11)") (class "Default")
      (node (ref "U5") (pin "11") (pinfunction "ALERT_1_11") (pintype "output"))
    )
    (net (code "118") (name "unconnected-(U5-ALERT_2-Pad12)") (class "Default")
      (node (ref "U5") (pin "12") (pinfunction "ALERT_2_12") (pintype "output"))
    )
    (net (code "119") (name "unconnected-(U5-ALERT_3-Pad14)") (class "Default")
      (node (ref "U5") (pin "14") (pinfunction "ALERT_3_14") (pintype "output"))
    )
    (net (code "120") (name "unconnected-(U5-ALERT_4-Pad15)") (class "Default")
      (node (ref "U5") (pin "15") (pinfunction "ALERT_4_15") (pintype "output"))
    )
    (net (code "121") (name "unconnected-(U6-INT2-Pad9)") (class "Default")
      (node (ref "U6") (pin "9") (pinfunction "INT2_9") (pintype "output"))
    )
    (net (code "122") (name "unconnected-(U6-RESV_2-Pad2)") (class "Default")
      (node (ref "U6") (pin "2") (pinfunction "RESV_2_2") (pintype "passive"))
    )
    (net (code "123") (name "unconnected-(U6-RESV_3-Pad3)") (class "Default")
      (node (ref "U6") (pin "3") (pinfunction "RESV_3_3") (pintype "passive"))
    )
    (net (code "124") (name "unconnected-(U6-RESV_10-Pad10)") (class "Default")
      (node (ref "U6") (pin "10") (pinfunction "RESV_10_10") (pintype "passive"))
    )
    (net (code "125") (name "unconnected-(U6-RESV_11-Pad11)") (class "Default")
      (node (ref "U6") (pin "11") (pinfunction "RESV_11_11") (pintype "passive"))
    )
    (net (code "126") (name "unconnected-(U7-ALERT_1-Pad11)") (class "Default")
      (node (ref "U7") (pin "11") (pinfunction "ALERT_1_11") (pintype "output"))
    )
    (net (code "127") (name "unconnected-(U7-ALERT_2-Pad12)") (class "Default")
      (node (ref "U7") (pin "12") (pinfunction "ALERT_2_12") (pintype "output"))
    )
    (net (code "128") (name "unconnected-(U7-ALERT_3-Pad14)") (class "Default")
      (node (ref "U7") (pin "14") (pinfunction "ALERT_3_14") (pintype "output"))
    )
    (net (code "129") (name "unconnected-(U7-ALERT_4-Pad15)") (class "Default")
      (node (ref "U7") (pin "15") (pinfunction "ALERT_4_15") (pintype "output"))
    )
    (net (code "130") (name "unconnected-(U8-ALERT_1-Pad11)") (class "Default")
      (node (ref "U8") (pin "11") (pinfunction "ALERT_1_11") (pintype "output"))
    )
    (net (code "131") (name "unconnected-(U8-ALERT_2-Pad12)") (class "Default")
      (node (ref "U8") (pin "12") (pinfunction "ALERT_2_12") (pintype "output"))
    )
    (net (code "132") (name "unconnected-(U8-ALERT_3-Pad14)") (class "Default")
      (node (ref "U8") (pin "14") (pinfunction "ALERT_3_14") (pintype "output"))
    )
    (net (code "133") (name "unconnected-(U8-ALERT_4-Pad15)") (class "Default")
      (node (ref "U8") (pin "15") (pinfunction "ALERT_4_15") (pintype "output"))
    )
    (net (code "134") (name "unconnected-(U9-ALERT_1-Pad11)") (class "Default")
      (node (ref "U9") (pin "11") (pinfunction "ALERT_1_11") (pintype "output"))
    )
    (net (code "135") (name "unconnected-(U9-ALERT_2-Pad12)") (class "Default")
      (node (ref "U9") (pin "12") (pinfunction "ALERT_2_12") (pintype "output"))
    )
    (net (code "136") (name "unconnected-(U9-ALERT_3-Pad14)") (class "Default")
      (node (ref "U9") (pin "14") (pinfunction "ALERT_3_14") (pintype "output"))
    )
    (net (code "137") (name "unconnected-(U9-ALERT_4-Pad15)") (class "Default")
      (node (ref "U9") (pin "15") (pinfunction "ALERT_4_15") (pintype "output"))
    )
    (net (code "138") (name "unconnected-(U10-ALERT_1-Pad11)") (class "Default")
      (node (ref "U10") (pin "11") (pinfunction "ALERT_1_11") (pintype "output"))
    )
    (net (code "139") (name "unconnected-(U10-ALERT_2-Pad12)") (class "Default")
      (node (ref "U10") (pin "12") (pinfunction "ALERT_2_12") (pintype "output"))
    )
    (net (code "140") (name "unconnected-(U10-ALERT_3-Pad14)") (class "Default")
      (node (ref "U10") (pin "14") (pinfunction "ALERT_3_14") (pintype "output"))
    )
    (net (code "141") (name "unconnected-(U10-ALERT_4-Pad15)") (class "Default")
      (node (ref "U10") (pin "15") (pinfunction "ALERT_4_15") (pintype "output"))
    )
    (net (code "142") (name "unconnected-(U13-P4-Pad4)") (class "Default")
      (node (ref "U13") (pin "4") (pinfunction "P4_4") (pintype "bidirectional"))
    )
    (net (code "143") (name "~{RESET}") (class "Default")
      (node (ref "JP1") (pin "16") (pinfunction "16_16") (pintype "passive"))
    )
  )
)
